# homeboard16.net
KiCad netlist of a schematic drawn in EAGLE
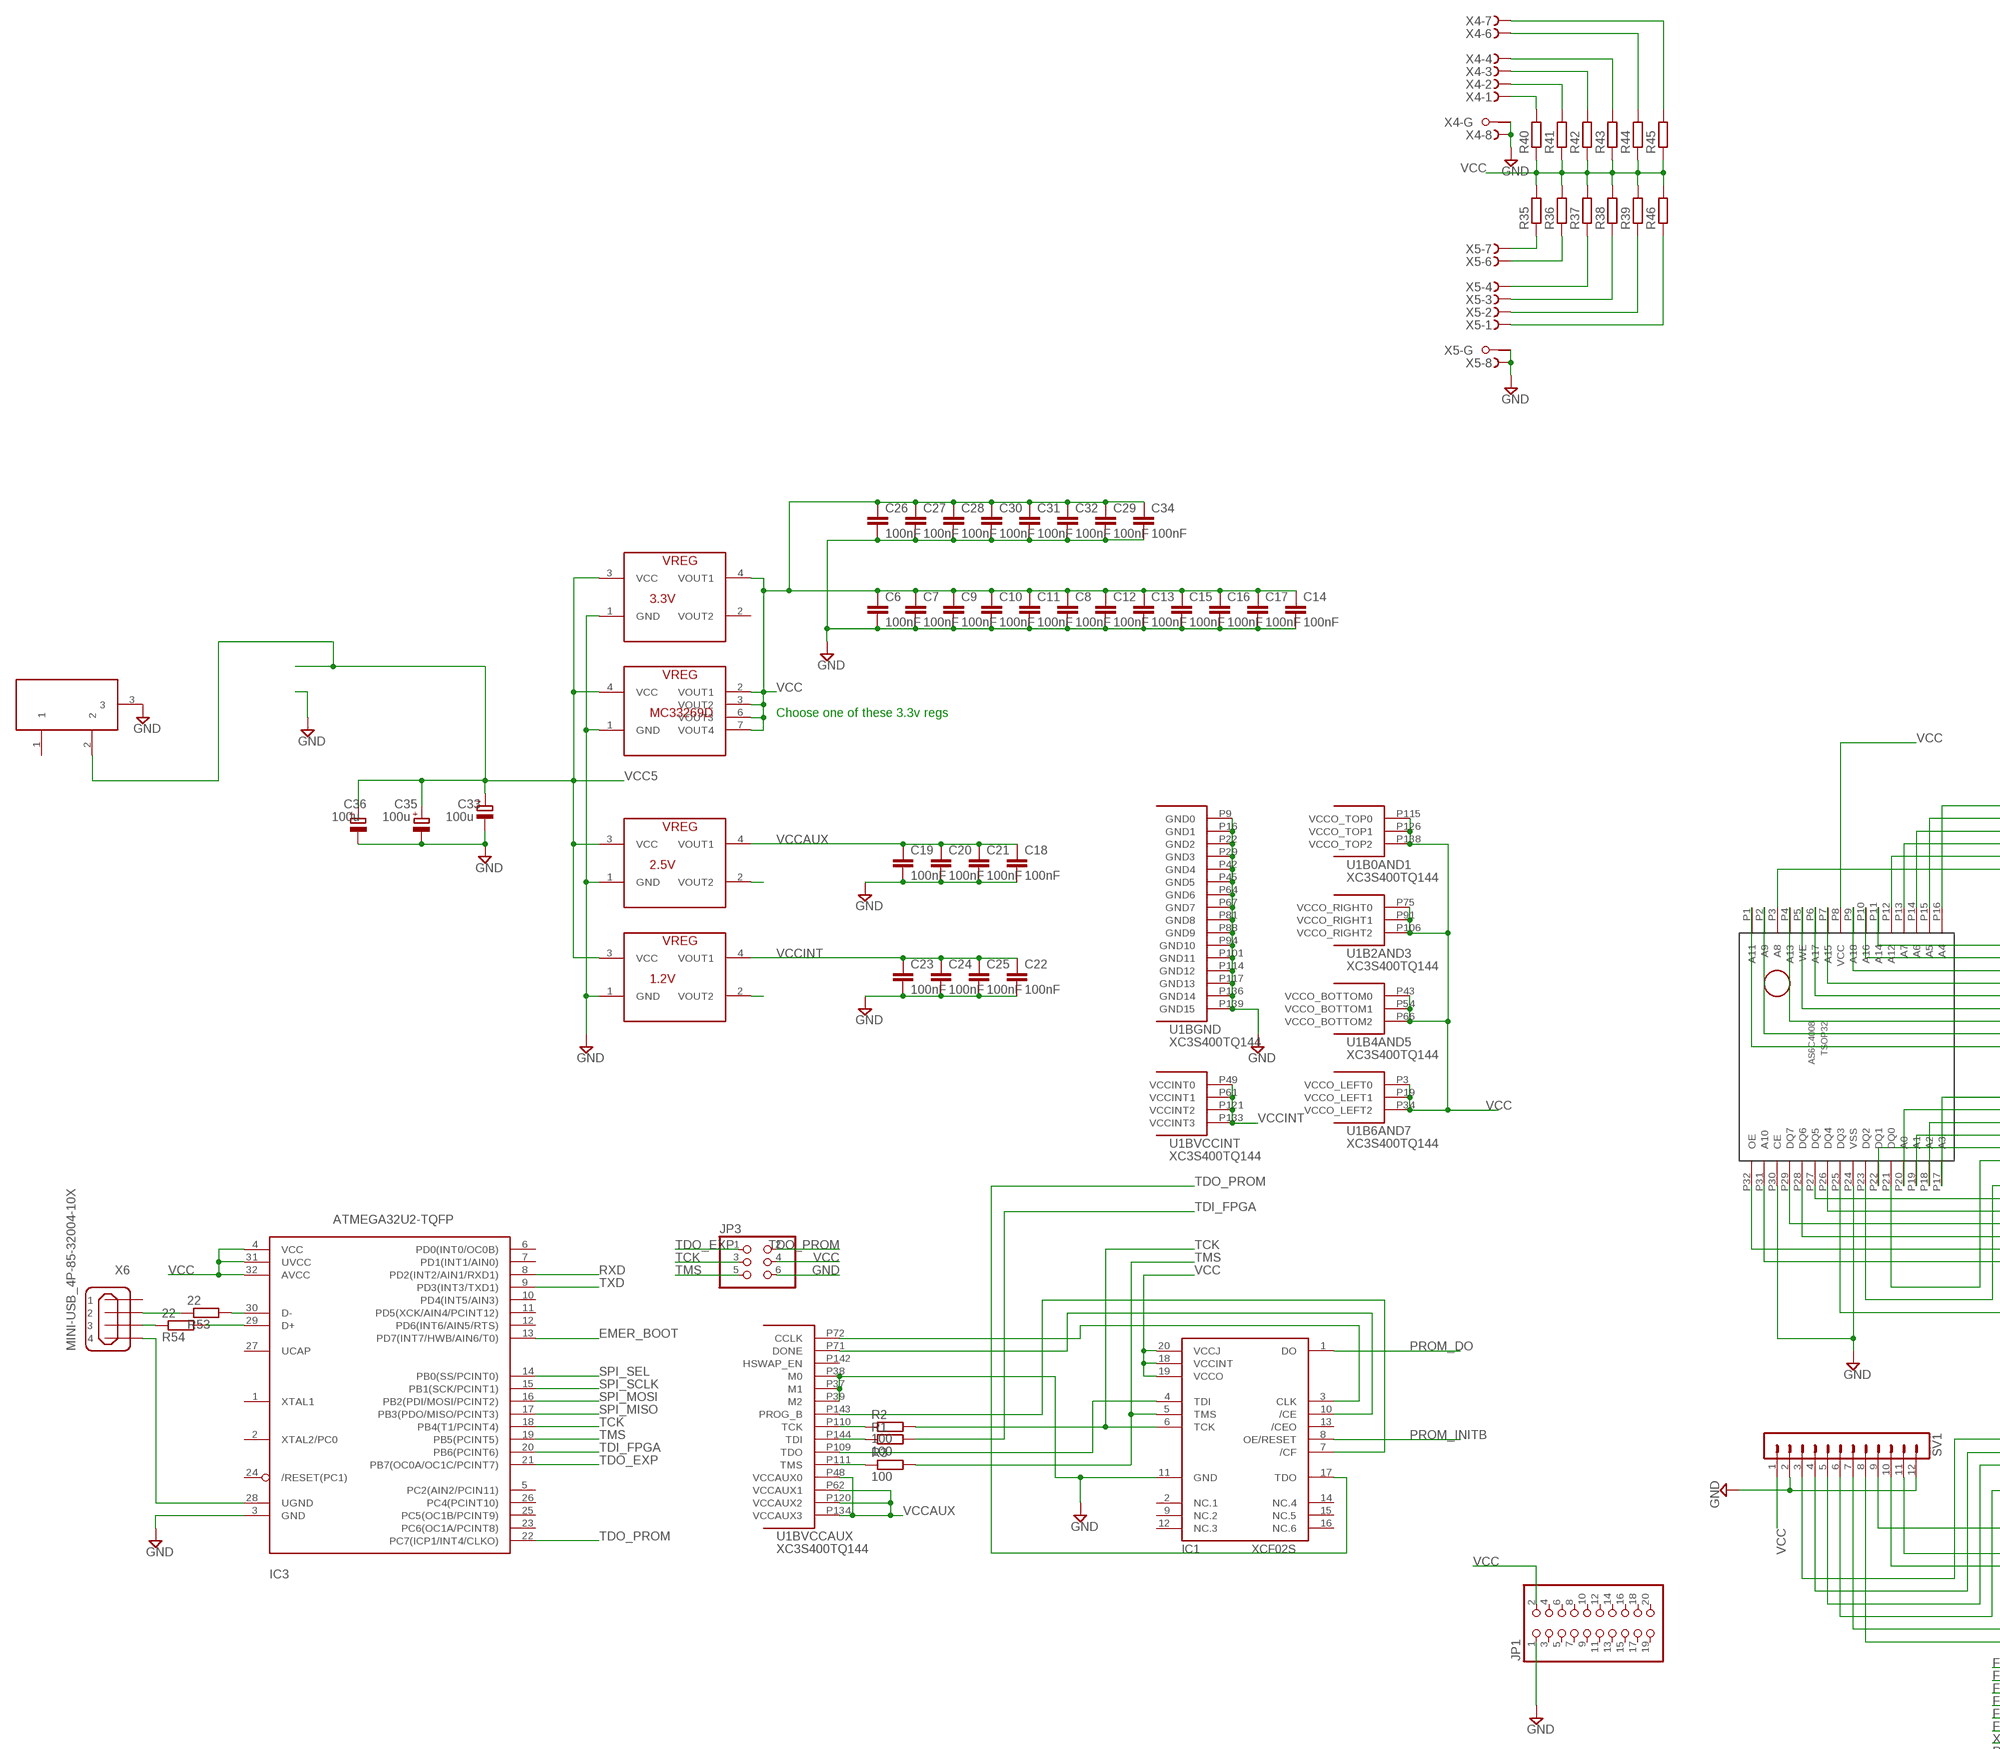
[diagram p0: schematic, sheet 1, part 1 of 3]
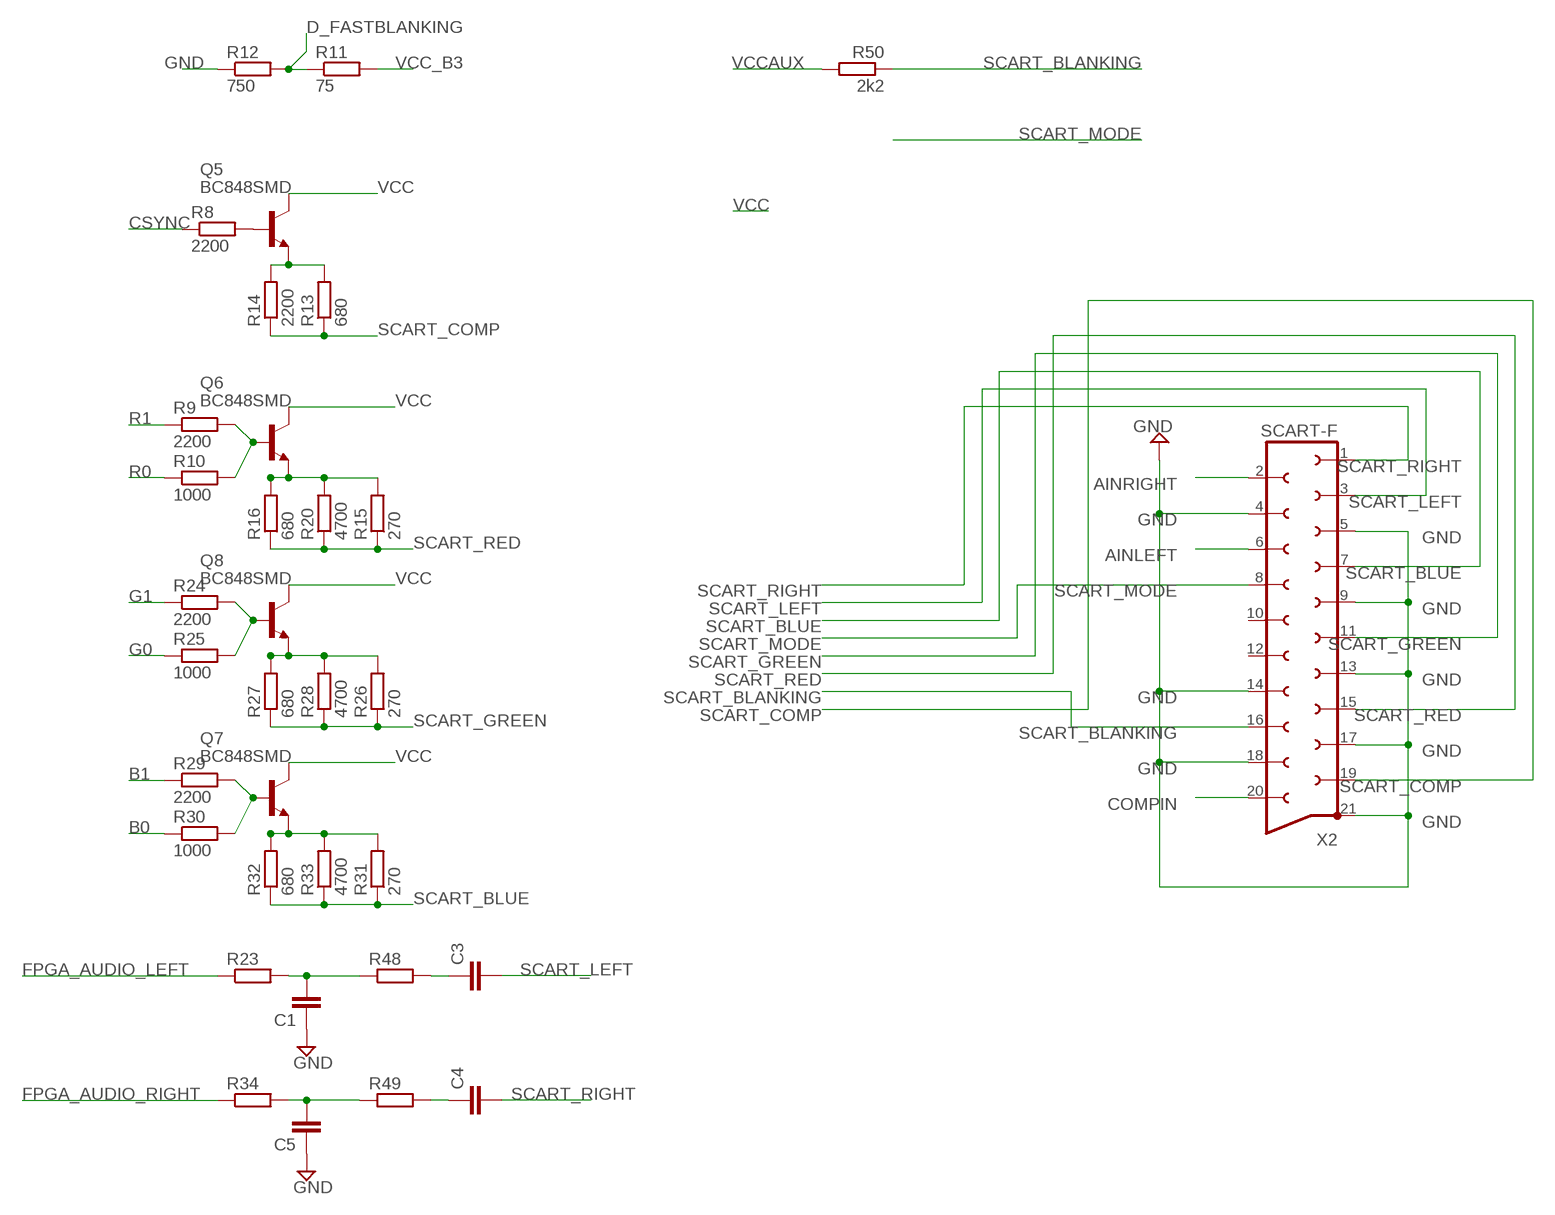
[diagram p1: schematic, sheet 1, part 2 of 3]
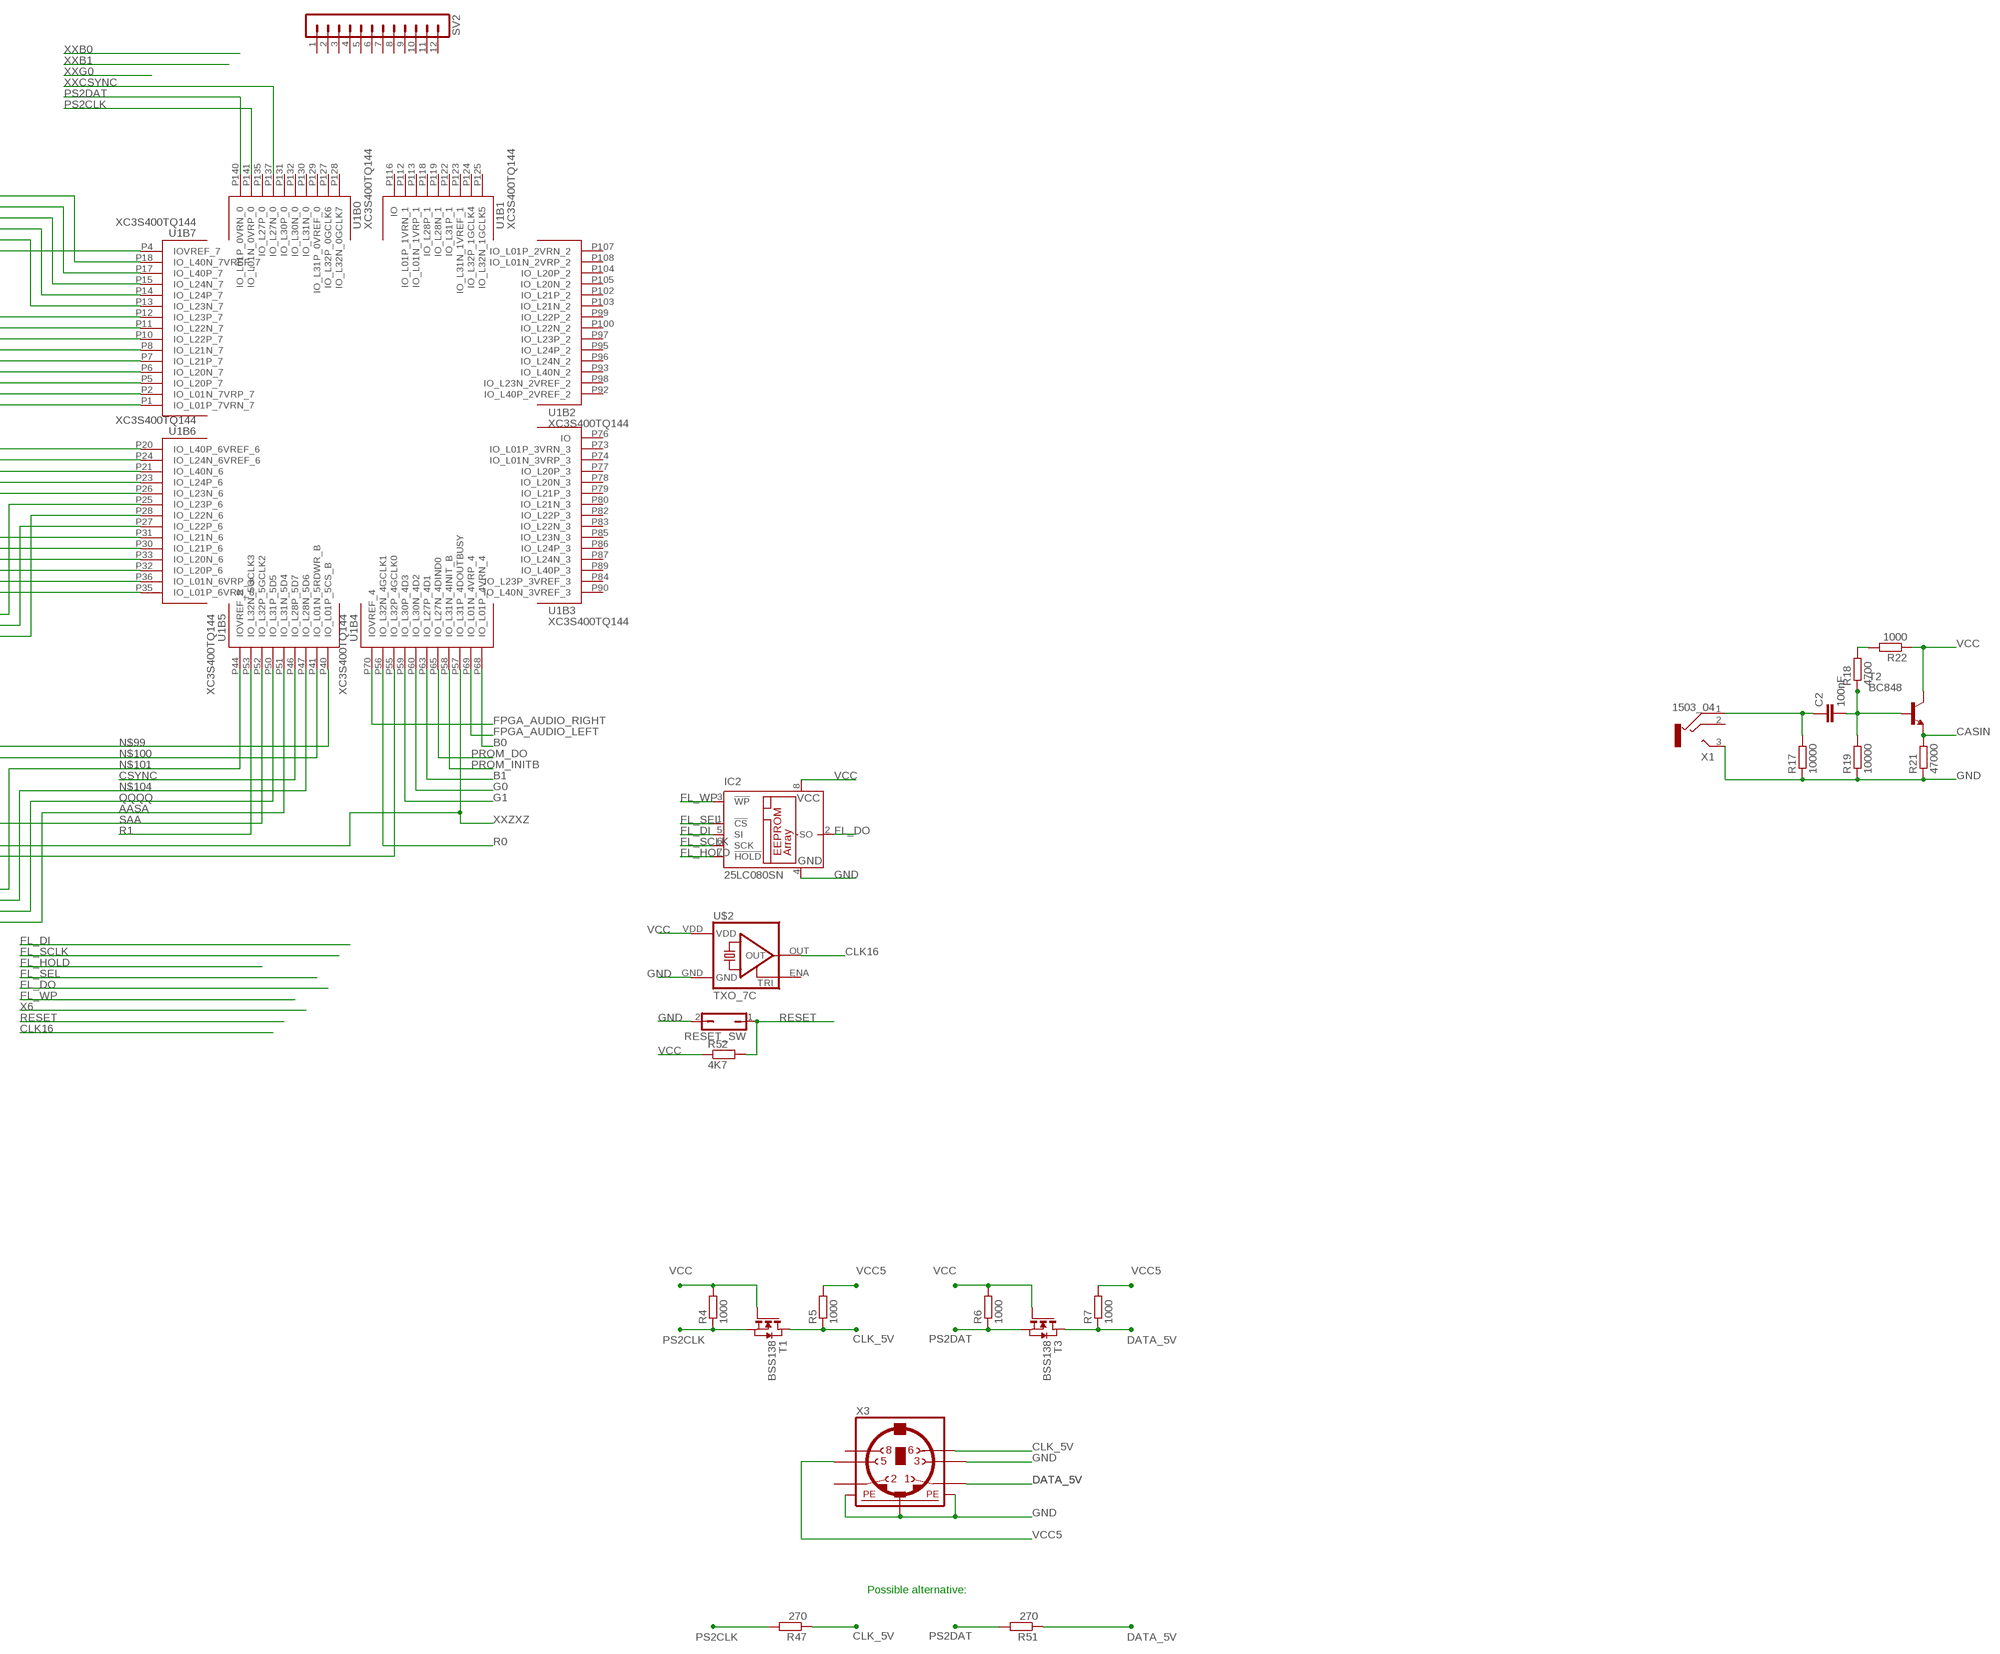
[diagram p2: schematic, sheet 1, part 3 of 3]

(export (version "E")
  (design (tool "Eeschema 10.0.6"))
  (components
    (comp (ref "C1")
      (value "C-EUC0603")
      (footprint "eagle-import:C0603")
      (libsource (lib "eagle-import") (part "resistor_C-EUC0603"))
    )
    (comp (ref "C2")
      (value "100nF")
      (footprint "eagle-import:C0603")
      (libsource (lib "eagle-import") (part "resistor_C-EUC0603"))
    )
    (comp (ref "C3")
      (value "C-EUC0603")
      (footprint "eagle-import:C0603")
      (libsource (lib "eagle-import") (part "resistor_C-EUC0603"))
    )
    (comp (ref "C4")
      (value "C-EUC0603")
      (footprint "eagle-import:C0603")
      (libsource (lib "eagle-import") (part "resistor_C-EUC0603"))
    )
    (comp (ref "C5")
      (value "C-EUC0603")
      (footprint "eagle-import:C0603")
      (libsource (lib "eagle-import") (part "resistor_C-EUC0603"))
    )
    (comp (ref "C6")
      (value "100nF")
      (footprint "eagle-import:C0603")
      (libsource (lib "eagle-import") (part "C-EUC0603"))
    )
    (comp (ref "C7")
      (value "100nF")
      (footprint "eagle-import:C0603")
      (libsource (lib "eagle-import") (part "C-EUC0603"))
    )
    (comp (ref "C8")
      (value "100nF")
      (footprint "eagle-import:C0603")
      (libsource (lib "eagle-import") (part "C-EUC0603"))
    )
    (comp (ref "C9")
      (value "100nF")
      (footprint "eagle-import:C0603")
      (libsource (lib "eagle-import") (part "C-EUC0603"))
    )
    (comp (ref "C10")
      (value "100nF")
      (footprint "eagle-import:C0603")
      (libsource (lib "eagle-import") (part "C-EUC0603"))
    )
    (comp (ref "C11")
      (value "100nF")
      (footprint "eagle-import:C0603")
      (libsource (lib "eagle-import") (part "C-EUC0603"))
    )
    (comp (ref "C12")
      (value "100nF")
      (footprint "eagle-import:C0603")
      (libsource (lib "eagle-import") (part "C-EUC0603"))
    )
    (comp (ref "C13")
      (value "100nF")
      (footprint "eagle-import:C0603")
      (libsource (lib "eagle-import") (part "C-EUC0603"))
    )
    (comp (ref "C14")
      (value "100nF")
      (footprint "eagle-import:C0603")
      (libsource (lib "eagle-import") (part "C-EUC0603"))
    )
    (comp (ref "C15")
      (value "100nF")
      (footprint "eagle-import:C0603")
      (libsource (lib "eagle-import") (part "C-EUC0603"))
    )
    (comp (ref "C16")
      (value "100nF")
      (footprint "eagle-import:C0603")
      (libsource (lib "eagle-import") (part "C-EUC0603"))
    )
    (comp (ref "C17")
      (value "100nF")
      (footprint "eagle-import:C0603")
      (libsource (lib "eagle-import") (part "C-EUC0603"))
    )
    (comp (ref "C18")
      (value "100nF")
      (footprint "eagle-import:C0603")
      (libsource (lib "eagle-import") (part "C-EUC0603"))
    )
    (comp (ref "C19")
      (value "100nF")
      (footprint "eagle-import:C0603")
      (libsource (lib "eagle-import") (part "C-EUC0603"))
    )
    (comp (ref "C20")
      (value "100nF")
      (footprint "eagle-import:C0603")
      (libsource (lib "eagle-import") (part "C-EUC0603"))
    )
    (comp (ref "C21")
      (value "100nF")
      (footprint "eagle-import:C0603")
      (libsource (lib "eagle-import") (part "C-EUC0603"))
    )
    (comp (ref "C22")
      (value "100nF")
      (footprint "eagle-import:C0603")
      (libsource (lib "eagle-import") (part "C-EUC0603"))
    )
    (comp (ref "C23")
      (value "100nF")
      (footprint "eagle-import:C0603")
      (libsource (lib "eagle-import") (part "C-EUC0603"))
    )
    (comp (ref "C24")
      (value "100nF")
      (footprint "eagle-import:C0603")
      (libsource (lib "eagle-import") (part "C-EUC0603"))
    )
    (comp (ref "C25")
      (value "100nF")
      (footprint "eagle-import:C0603")
      (libsource (lib "eagle-import") (part "C-EUC0603"))
    )
    (comp (ref "C26")
      (value "100nF")
      (footprint "eagle-import:C0603")
      (libsource (lib "eagle-import") (part "C-EUC0603"))
    )
    (comp (ref "C27")
      (value "100nF")
      (footprint "eagle-import:C0603")
      (libsource (lib "eagle-import") (part "C-EUC0603"))
    )
    (comp (ref "C28")
      (value "100nF")
      (footprint "eagle-import:C0603")
      (libsource (lib "eagle-import") (part "C-EUC0603"))
    )
    (comp (ref "C29")
      (value "100nF")
      (footprint "eagle-import:C0603")
      (libsource (lib "eagle-import") (part "C-EUC0603"))
    )
    (comp (ref "C30")
      (value "100nF")
      (footprint "eagle-import:C0603")
      (libsource (lib "eagle-import") (part "C-EUC0603"))
    )
    (comp (ref "C31")
      (value "100nF")
      (footprint "eagle-import:C0603")
      (libsource (lib "eagle-import") (part "C-EUC0603"))
    )
    (comp (ref "C32")
      (value "100nF")
      (footprint "eagle-import:C0603")
      (libsource (lib "eagle-import") (part "C-EUC0603"))
    )
    (comp (ref "C33")
      (value "100u")
      (footprint "eagle-import:PANASONIC_D")
      (libsource (lib "eagle-import") (part "CPOL-EUD"))
    )
    (comp (ref "C34")
      (value "100nF")
      (footprint "eagle-import:C0603")
      (libsource (lib "eagle-import") (part "C-EUC0603"))
    )
    (comp (ref "C35")
      (value "100u")
      (footprint "eagle-import:PANASONIC_D")
      (libsource (lib "eagle-import") (part "CPOL-EUD"))
    )
    (comp (ref "C36")
      (value "100u")
      (footprint "eagle-import:PANASONIC_D")
      (libsource (lib "eagle-import") (part "CPOL-EUD"))
    )
    (comp (ref "IC1")
      (value "XCF02S")
      (footprint "eagle-import:VO20")
      (libsource (lib "eagle-import") (part "XCF02S"))
    )
    (comp (ref "IC2")
      (value "25LC080SN")
      (footprint "eagle-import:SO-08")
      (fields (field (name "MF") "MICROCHIP") (field (name "MPN") "25LC080/SN"))
      (libsource (lib "eagle-import") (part "25SNLC080"))
    )
    (comp (ref "IC3")
      (value "ATMEGA32U2-TQFP")
      (footprint "eagle-import:TQFP32-08")
      (libsource (lib "eagle-import") (part "ATMEGA32U2-TQFP"))
    )
    (comp (ref "JP1")
      (value "PINHD-2X10")
      (footprint "eagle-import:2X10")
      (libsource (lib "eagle-import") (part "PINHD-2X10"))
    )
    (comp (ref "JP3")
      (value "PINHD-2X3")
      (footprint "eagle-import:2X03")
      (libsource (lib "eagle-import") (part "PINHD-2X3"))
    )
    (comp (ref "Q5")
      (value "BC848SMD")
      (footprint "eagle-import:SOT23")
      (libsource (lib "eagle-import") (part "BC848SMD"))
    )
    (comp (ref "Q6")
      (value "BC848SMD")
      (footprint "eagle-import:SOT23")
      (libsource (lib "eagle-import") (part "BC848SMD"))
    )
    (comp (ref "Q7")
      (value "BC848SMD")
      (footprint "eagle-import:SOT23")
      (libsource (lib "eagle-import") (part "BC848SMD"))
    )
    (comp (ref "Q8")
      (value "BC848SMD")
      (footprint "eagle-import:SOT23")
      (libsource (lib "eagle-import") (part "BC848SMD"))
    )
    (comp (ref "R1")
      (value "100")
      (footprint "eagle-import:R0805")
      (libsource (lib "eagle-import") (part "R-EU_R0805"))
    )
    (comp (ref "R2")
      (value "100")
      (footprint "eagle-import:R0805")
      (libsource (lib "eagle-import") (part "R-EU_R0805"))
    )
    (comp (ref "R3")
      (value "100")
      (footprint "eagle-import:R0805")
      (libsource (lib "eagle-import") (part "R-EU_R0805"))
    )
    (comp (ref "R4")
      (value "1000")
      (footprint "eagle-import:R0805")
      (libsource (lib "eagle-import") (part "R-EU_R0805"))
    )
    (comp (ref "R5")
      (value "1000")
      (footprint "eagle-import:R0805")
      (libsource (lib "eagle-import") (part "R-EU_R0805"))
    )
    (comp (ref "R6")
      (value "1000")
      (footprint "eagle-import:R0805")
      (libsource (lib "eagle-import") (part "R-EU_R0805"))
    )
    (comp (ref "R7")
      (value "1000")
      (footprint "eagle-import:R0805")
      (libsource (lib "eagle-import") (part "R-EU_R0805"))
    )
    (comp (ref "R8")
      (value "2200")
      (footprint "eagle-import:R0805")
      (libsource (lib "eagle-import") (part "R-EU_R0805"))
    )
    (comp (ref "R9")
      (value "2200")
      (footprint "eagle-import:R0805")
      (libsource (lib "eagle-import") (part "R-EU_R0805"))
    )
    (comp (ref "R10")
      (value "1000")
      (footprint "eagle-import:R0805")
      (libsource (lib "eagle-import") (part "R-EU_R0805"))
    )
    (comp (ref "R11")
      (value "75")
      (footprint "eagle-import:R0805")
      (libsource (lib "eagle-import") (part "R-EU_R0805"))
    )
    (comp (ref "R12")
      (value "750")
      (footprint "eagle-import:R0805")
      (libsource (lib "eagle-import") (part "R-EU_R0805"))
    )
    (comp (ref "R13")
      (value "680")
      (footprint "eagle-import:R0805")
      (libsource (lib "eagle-import") (part "R-EU_R0805"))
    )
    (comp (ref "R14")
      (value "2200")
      (footprint "eagle-import:R0805")
      (libsource (lib "eagle-import") (part "R-EU_R0805"))
    )
    (comp (ref "R15")
      (value "270")
      (footprint "eagle-import:R0805")
      (libsource (lib "eagle-import") (part "R-EU_R0805"))
    )
    (comp (ref "R16")
      (value "680")
      (footprint "eagle-import:R0805")
      (libsource (lib "eagle-import") (part "R-EU_R0805"))
    )
    (comp (ref "R17")
      (value "10000")
      (footprint "eagle-import:R0805")
      (libsource (lib "eagle-import") (part "R-EU_R0805"))
    )
    (comp (ref "R18")
      (value "4700")
      (footprint "eagle-import:R0805")
      (libsource (lib "eagle-import") (part "R-EU_R0805"))
    )
    (comp (ref "R19")
      (value "10000")
      (footprint "eagle-import:R0805")
      (libsource (lib "eagle-import") (part "R-EU_R0805"))
    )
    (comp (ref "R20")
      (value "4700")
      (footprint "eagle-import:R0805")
      (libsource (lib "eagle-import") (part "R-EU_R0805"))
    )
    (comp (ref "R21")
      (value "47000")
      (footprint "eagle-import:R0805")
      (libsource (lib "eagle-import") (part "R-EU_R0805"))
    )
    (comp (ref "R22")
      (value "1000")
      (footprint "eagle-import:R0805")
      (libsource (lib "eagle-import") (part "R-EU_R0805"))
    )
    (comp (ref "R23")
      (value "R-EU_M0805")
      (footprint "eagle-import:M0805")
      (libsource (lib "eagle-import") (part "resistor_R-EU_M0805"))
    )
    (comp (ref "R24")
      (value "2200")
      (footprint "eagle-import:R0805")
      (libsource (lib "eagle-import") (part "R-EU_R0805"))
    )
    (comp (ref "R25")
      (value "1000")
      (footprint "eagle-import:R0805")
      (libsource (lib "eagle-import") (part "R-EU_R0805"))
    )
    (comp (ref "R26")
      (value "270")
      (footprint "eagle-import:R0805")
      (libsource (lib "eagle-import") (part "R-EU_R0805"))
    )
    (comp (ref "R27")
      (value "680")
      (footprint "eagle-import:R0805")
      (libsource (lib "eagle-import") (part "R-EU_R0805"))
    )
    (comp (ref "R28")
      (value "4700")
      (footprint "eagle-import:R0805")
      (libsource (lib "eagle-import") (part "R-EU_R0805"))
    )
    (comp (ref "R29")
      (value "2200")
      (footprint "eagle-import:R0805")
      (libsource (lib "eagle-import") (part "R-EU_R0805"))
    )
    (comp (ref "R30")
      (value "1000")
      (footprint "eagle-import:R0805")
      (libsource (lib "eagle-import") (part "R-EU_R0805"))
    )
    (comp (ref "R31")
      (value "270")
      (footprint "eagle-import:R0805")
      (libsource (lib "eagle-import") (part "R-EU_R0805"))
    )
    (comp (ref "R32")
      (value "680")
      (footprint "eagle-import:R0805")
      (libsource (lib "eagle-import") (part "R-EU_R0805"))
    )
    (comp (ref "R33")
      (value "4700")
      (footprint "eagle-import:R0805")
      (libsource (lib "eagle-import") (part "R-EU_R0805"))
    )
    (comp (ref "R34")
      (value "R-EU_M0805")
      (footprint "eagle-import:M0805")
      (libsource (lib "eagle-import") (part "resistor_R-EU_M0805"))
    )
    (comp (ref "R35")
      (value "R-EU_M0805")
      (footprint "eagle-import:M0805")
      (libsource (lib "eagle-import") (part "resistor_R-EU_M0805"))
    )
    (comp (ref "R36")
      (value "R-EU_M0805")
      (footprint "eagle-import:M0805")
      (libsource (lib "eagle-import") (part "resistor_R-EU_M0805"))
    )
    (comp (ref "R37")
      (value "R-EU_M0805")
      (footprint "eagle-import:M0805")
      (libsource (lib "eagle-import") (part "resistor_R-EU_M0805"))
    )
    (comp (ref "R38")
      (value "R-EU_M0805")
      (footprint "eagle-import:M0805")
      (libsource (lib "eagle-import") (part "resistor_R-EU_M0805"))
    )
    (comp (ref "R39")
      (value "R-EU_M0805")
      (footprint "eagle-import:M0805")
      (libsource (lib "eagle-import") (part "resistor_R-EU_M0805"))
    )
    (comp (ref "R40")
      (value "R-EU_M0805")
      (footprint "eagle-import:M0805")
      (libsource (lib "eagle-import") (part "resistor_R-EU_M0805"))
    )
    (comp (ref "R41")
      (value "R-EU_M0805")
      (footprint "eagle-import:M0805")
      (libsource (lib "eagle-import") (part "resistor_R-EU_M0805"))
    )
    (comp (ref "R42")
      (value "R-EU_M0805")
      (footprint "eagle-import:M0805")
      (libsource (lib "eagle-import") (part "resistor_R-EU_M0805"))
    )
    (comp (ref "R43")
      (value "R-EU_M0805")
      (footprint "eagle-import:M0805")
      (libsource (lib "eagle-import") (part "resistor_R-EU_M0805"))
    )
    (comp (ref "R44")
      (value "R-EU_M0805")
      (footprint "eagle-import:M0805")
      (libsource (lib "eagle-import") (part "resistor_R-EU_M0805"))
    )
    (comp (ref "R45")
      (value "R-EU_M0805")
      (footprint "eagle-import:M0805")
      (libsource (lib "eagle-import") (part "resistor_R-EU_M0805"))
    )
    (comp (ref "R46")
      (value "R-EU_M0805")
      (footprint "eagle-import:M0805")
      (libsource (lib "eagle-import") (part "resistor_R-EU_M0805"))
    )
    (comp (ref "R47")
      (value "270")
      (footprint "eagle-import:R0805")
      (libsource (lib "eagle-import") (part "R-EU_R0805"))
    )
    (comp (ref "R48")
      (value "R-EU_M0805")
      (footprint "eagle-import:M0805")
      (libsource (lib "eagle-import") (part "resistor_R-EU_M0805"))
    )
    (comp (ref "R49")
      (value "R-EU_M0805")
      (footprint "eagle-import:M0805")
      (libsource (lib "eagle-import") (part "resistor_R-EU_M0805"))
    )
    (comp (ref "R50")
      (value "2k2")
      (footprint "eagle-import:M0805")
      (libsource (lib "eagle-import") (part "resistor_R-EU_M0805"))
    )
    (comp (ref "R51")
      (value "270")
      (footprint "eagle-import:R0805")
      (libsource (lib "eagle-import") (part "R-EU_R0805"))
    )
    (comp (ref "R52")
      (value "4K7")
      (footprint "eagle-import:M0805")
      (libsource (lib "eagle-import") (part "resistor_R-EU_M0805"))
    )
    (comp (ref "R53")
      (value "22")
      (footprint "eagle-import:R0805")
      (libsource (lib "eagle-import") (part "R-EU_R0805"))
    )
    (comp (ref "R54")
      (value "22")
      (footprint "eagle-import:R0805")
      (libsource (lib "eagle-import") (part "R-EU_R0805"))
    )
    (comp (ref "REG1.2")
      (value "1.2V")
      (footprint "eagle-import:SOT223")
      (libsource (lib "eagle-import") (part "NX1117"))
    )
    (comp (ref "REG2.5")
      (value "2.5V")
      (footprint "eagle-import:SOT223")
      (libsource (lib "eagle-import") (part "NX1117"))
    )
    (comp (ref "RESET_SW")
      (value "JP1Q")
      (footprint "eagle-import:JP1")
      (libsource (lib "eagle-import") (part "JP1Q"))
    )
    (comp (ref "SV1")
      (value "MA12-1")
      (footprint "eagle-import:MA12-1")
      (libsource (lib "eagle-import") (part "MA12-1"))
    )
    (comp (ref "SV2")
      (value "MA12-1")
      (footprint "eagle-import:MA12-1")
      (fields (field (name "OC_FARNELL") "unknown") (field (name "OC_NEWARK") "unknown"))
      (libsource (lib "eagle-import") (part "MA12-1"))
    )
    (comp (ref "T1")
      (value "BSS138")
      (footprint "eagle-import:SOT-23")
      (libsource (lib "eagle-import") (part "NMOSSOT23"))
    )
    (comp (ref "T2")
      (value "BC848")
      (footprint "eagle-import:SOT23")
      (libsource (lib "eagle-import") (part "BC848"))
    )
    (comp (ref "T3")
      (value "BSS138")
      (footprint "eagle-import:SOT-23")
      (libsource (lib "eagle-import") (part "NMOSSOT23"))
    )
    (comp (ref "U$2")
      (value "TXO_7C")
      (footprint "eagle-import:OSC_7C")
      (libsource (lib "eagle-import") (part "TXO_7C"))
    )
    (comp (ref "U$4")
      (value "3.3V")
      (footprint "eagle-import:SOT223")
      (libsource (lib "eagle-import") (part "NX1117"))
    )
    (comp (ref "U$5")
      (value "MC33269D")
      (footprint "eagle-import:SO8")
      (libsource (lib "eagle-import") (part "MC33269D"))
    )
    (comp (ref "U$6")
      (value "AS6C4008")
      (footprint "eagle-import:TSOP32")
      (libsource (lib "eagle-import") (part "AS6C4008"))
    )
    (comp (ref "U1")
      (value "XC3S400TQ144")
      (footprint "eagle-import:TQ144")
      (libsource (lib "eagle-import") (part "XC3S400TQ144"))
    )
    (comp (ref "X1")
      (value "1503_04")
      (footprint "eagle-import:1503_04")
      (libsource (lib "eagle-import") (part "1503_04"))
    )
    (comp (ref "X2")
      (value "SCART-F")
      (footprint "eagle-import:SCART-F")
      (libsource (lib "eagle-import") (part "SCART-F"))
    )
    (comp (ref "X3")
      (value "MINI_DIN_6")
      (footprint "eagle-import:M_DIN6")
      (libsource (lib "eagle-import") (part "MINI_DIN_6"))
    )
    (comp (ref "X4")
      (value "F09HPS")
      (footprint "eagle-import:F09HP")
      (libsource (lib "eagle-import") (part "F09HPS"))
    )
    (comp (ref "X5")
      (value "F09HPS")
      (footprint "eagle-import:F09HP")
      (libsource (lib "eagle-import") (part "F09HPS"))
    )
    (comp (ref "X6")
      (value "MINI-USB_4P-85-32004-10X")
      (footprint "eagle-import:85-32004-10X")
      (libsource (lib "eagle-import") (part "MINI-USB_4P-85-32004-10X"))
    )
    (comp (ref "X7")
      (value "DC21MMX")
      (footprint "eagle-import:DC-21MM")
      (libsource (lib "eagle-import") (part "DC21MMX"))
    )
  )
  (nets
    (net (code "1") (name "/1") (class "Default")
      (node (ref "X7") (pin "1") (pinfunction "1_1") (pintype "power_in"))
    )
    (net (code "2") (name "/AASA") (class "Default")
      (node (ref "SV1") (pin "8") (pinfunction "8_8") (pintype "passive"))
      (node (ref "U1") (pin "P51") (pinfunction "IO_L31N_5D4_P51") (pintype "bidirectional"))
    )
    (net (code "3") (name "/AINLEFT") (class "Default")
      (node (ref "X2") (pin "6") (pinfunction "6_6") (pintype "passive"))
    )
    (net (code "4") (name "/AINRIGHT") (class "Default")
      (node (ref "X2") (pin "2") (pinfunction "2_2") (pintype "passive"))
    )
    (net (code "5") (name "/B0") (class "Default")
      (node (ref "R30") (pin "1") (pinfunction "1_1") (pintype "passive"))
      (node (ref "U1") (pin "P68") (pinfunction "IO_L01P_4VRN_4_P68") (pintype "bidirectional"))
    )
    (net (code "6") (name "/B1") (class "Default")
      (node (ref "R29") (pin "1") (pinfunction "1_1") (pintype "passive"))
      (node (ref "U1") (pin "P63") (pinfunction "IO_L27P_4D1_P63") (pintype "bidirectional"))
    )
    (net (code "7") (name "/CASIN") (class "Default")
      (node (ref "R21") (pin "2") (pinfunction "2_2") (pintype "passive"))
      (node (ref "T2") (pin "2") (pinfunction "E_2") (pintype "passive"))
    )
    (net (code "8") (name "/CLK16") (class "Default")
      (node (ref "U$2") (pin "OUT") (pinfunction "OUT_OUT") (pintype "output"))
    )
    (net (code "9") (name "/CLK_5V") (class "Default")
      (node (ref "R47") (pin "1") (pinfunction "1_1") (pintype "passive"))
      (node (ref "R5") (pin "1") (pinfunction "1_1") (pintype "passive"))
      (node (ref "T1") (pin "1") (pinfunction "D_1") (pintype "passive"))
      (node (ref "X3") (pin "6") (pinfunction "6_6") (pintype "passive"))
    )
    (net (code "10") (name "/COMPIN") (class "Default")
      (node (ref "X2") (pin "20") (pinfunction "20_20") (pintype "passive"))
    )
    (net (code "11") (name "/CSYNC") (class "Default")
      (node (ref "R8") (pin "1") (pinfunction "1_1") (pintype "passive"))
      (node (ref "U1") (pin "P46") (pinfunction "IO_L28P_5D7_P46") (pintype "bidirectional"))
    )
    (net (code "12") (name "/DATA_5V") (class "Default")
      (node (ref "R51") (pin "1") (pinfunction "1_1") (pintype "passive"))
      (node (ref "R7") (pin "1") (pinfunction "1_1") (pintype "passive"))
      (node (ref "T3") (pin "1") (pinfunction "D_1") (pintype "passive"))
      (node (ref "X3") (pin "1") (pinfunction "1_1") (pintype "passive"))
    )
    (net (code "13") (name "/D_FASTBLANKING") (class "Default")
      (node (ref "R11") (pin "1") (pinfunction "1_1") (pintype "passive"))
      (node (ref "R12") (pin "2") (pinfunction "2_2") (pintype "passive"))
    )
    (net (code "14") (name "/EMER_BOOT") (class "Default")
      (node (ref "IC3") (pin "13") (pinfunction "PD7(INT7/HWB/AIN6/T0)_13") (pintype "bidirectional"))
    )
    (net (code "15") (name "/FL_DI") (class "Default")
      (node (ref "IC2") (pin "5") (pinfunction "SI_5") (pintype "input"))
    )
    (net (code "16") (name "/FL_DO") (class "Default")
      (node (ref "IC2") (pin "2") (pinfunction "SO_2") (pintype "bidirectional"))
    )
    (net (code "17") (name "/FL_HOLD") (class "Default")
      (node (ref "IC2") (pin "7") (pinfunction "~{HOLD}_7") (pintype "input"))
    )
    (net (code "18") (name "/FL_SCLK") (class "Default")
      (node (ref "IC2") (pin "6") (pinfunction "SCK_6") (pintype "input"))
    )
    (net (code "19") (name "/FL_SEL") (class "Default")
      (node (ref "IC2") (pin "1") (pinfunction "~{CS}_1") (pintype "input"))
    )
    (net (code "20") (name "/FL_WP") (class "Default")
      (node (ref "IC2") (pin "3") (pinfunction "~{WP}_3") (pintype "input"))
    )
    (net (code "21") (name "/FPGA_AUDIO_LEFT") (class "Default")
      (node (ref "R23") (pin "1") (pinfunction "1_1") (pintype "passive"))
      (node (ref "U1") (pin "P69") (pinfunction "IO_L01N_4VRP_4_P69") (pintype "bidirectional"))
    )
    (net (code "22") (name "/FPGA_AUDIO_RIGHT") (class "Default")
      (node (ref "R34") (pin "1") (pinfunction "1_1") (pintype "passive"))
      (node (ref "U1") (pin "P70") (pinfunction "IOVREF_4_P70") (pintype "bidirectional"))
    )
    (net (code "23") (name "/G0") (class "Default")
      (node (ref "R25") (pin "1") (pinfunction "1_1") (pintype "passive"))
      (node (ref "U1") (pin "P60") (pinfunction "IO_L30N_4D2_P60") (pintype "bidirectional"))
    )
    (net (code "24") (name "/G1") (class "Default")
      (node (ref "R24") (pin "1") (pinfunction "1_1") (pintype "passive"))
      (node (ref "U1") (pin "P59") (pinfunction "IO_L30P_4D3_P59") (pintype "bidirectional"))
    )
    (net (code "25") (name "/N$99") (class "Default")
      (node (ref "SV1") (pin "3") (pinfunction "3_3") (pintype "passive"))
      (node (ref "U1") (pin "P40") (pinfunction "IO_L01P_5CS_B_P40") (pintype "bidirectional"))
    )
    (net (code "26") (name "/N$100") (class "Default")
      (node (ref "SV1") (pin "4") (pinfunction "4_4") (pintype "passive"))
      (node (ref "U1") (pin "P41") (pinfunction "IO_L01N_5RDWR_B_P41") (pintype "bidirectional"))
    )
    (net (code "27") (name "/N$101") (class "Default")
      (node (ref "SV1") (pin "5") (pinfunction "5_5") (pintype "passive"))
      (node (ref "U1") (pin "P44") (pinfunction "IOVREF_5_P44") (pintype "bidirectional"))
    )
    (net (code "28") (name "/N$104") (class "Default")
      (node (ref "SV1") (pin "6") (pinfunction "6_6") (pintype "passive"))
      (node (ref "U1") (pin "P47") (pinfunction "IO_L28N_5D6_P47") (pintype "bidirectional"))
    )
    (net (code "29") (name "/PROM_DO") (class "Default")
      (node (ref "IC1") (pin "1") (pinfunction "DO_1") (pintype "bidirectional"))
      (node (ref "U1") (pin "P65") (pinfunction "IO_L27N_4DIND0_P65") (pintype "bidirectional"))
    )
    (net (code "30") (name "/PROM_INITB") (class "Default")
      (node (ref "IC1") (pin "8") (pinfunction "OE/RESET_8") (pintype "bidirectional"))
      (node (ref "U1") (pin "P58") (pinfunction "IO_L31N_4INIT_B_P58") (pintype "bidirectional"))
    )
    (net (code "31") (name "/PS2CLK") (class "Default")
      (node (ref "R4") (pin "1") (pinfunction "1_1") (pintype "passive"))
      (node (ref "R47") (pin "2") (pinfunction "2_2") (pintype "passive"))
      (node (ref "T1") (pin "2") (pinfunction "S_2") (pintype "passive"))
      (node (ref "U1") (pin "P141") (pinfunction "IO_L01N_0VRP_0_P141") (pintype "bidirectional"))
    )
    (net (code "32") (name "/PS2DAT") (class "Default")
      (node (ref "R51") (pin "2") (pinfunction "2_2") (pintype "passive"))
      (node (ref "R6") (pin "1") (pinfunction "1_1") (pintype "passive"))
      (node (ref "T3") (pin "2") (pinfunction "S_2") (pintype "passive"))
      (node (ref "U1") (pin "P140") (pinfunction "IO_L01P_0VRN_0_P140") (pintype "bidirectional"))
    )
    (net (code "33") (name "/QQQQ") (class "Default")
      (node (ref "SV1") (pin "7") (pinfunction "7_7") (pintype "passive"))
      (node (ref "U1") (pin "P50") (pinfunction "IO_L31P_5D5_P50") (pintype "bidirectional"))
    )
    (net (code "34") (name "/R0") (class "Default")
      (node (ref "R10") (pin "1") (pinfunction "1_1") (pintype "passive"))
      (node (ref "U1") (pin "P56") (pinfunction "IO_L32N_4GCLK1_P56") (pintype "bidirectional"))
    )
    (net (code "35") (name "/R1") (class "Default")
      (node (ref "R9") (pin "1") (pinfunction "1_1") (pintype "passive"))
      (node (ref "U1") (pin "P53") (pinfunction "IO_L32N_5GCLK3_P53") (pintype "bidirectional"))
    )
    (net (code "36") (name "/RESET") (class "Default")
      (node (ref "R52") (pin "2") (pinfunction "2_2") (pintype "passive"))
      (node (ref "RESET_SW") (pin "1") (pinfunction "1_1") (pintype "passive"))
    )
    (net (code "37") (name "/RXD") (class "Default")
      (node (ref "IC3") (pin "8") (pinfunction "PD2(INT2/AIN1/RXD1)_8") (pintype "bidirectional"))
    )
    (net (code "38") (name "/SAA") (class "Default")
      (node (ref "SV1") (pin "9") (pinfunction "9_9") (pintype "passive"))
      (node (ref "U1") (pin "P52") (pinfunction "IO_L32P_5GCLK2_P52") (pintype "bidirectional"))
    )
    (net (code "39") (name "/SCART_BLANKING") (class "Default")
      (node (ref "R50") (pin "1") (pinfunction "1_1") (pintype "passive"))
      (node (ref "X2") (pin "16") (pinfunction "16_16") (pintype "passive"))
    )
    (net (code "40") (name "/SCART_BLUE") (class "Default")
      (node (ref "R31") (pin "1") (pinfunction "1_1") (pintype "passive"))
      (node (ref "R32") (pin "1") (pinfunction "1_1") (pintype "passive"))
      (node (ref "R33") (pin "1") (pinfunction "1_1") (pintype "passive"))
      (node (ref "X2") (pin "7") (pinfunction "7_7") (pintype "passive"))
    )
    (net (code "41") (name "/SCART_COMP") (class "Default")
      (node (ref "R13") (pin "1") (pinfunction "1_1") (pintype "passive"))
      (node (ref "R14") (pin "1") (pinfunction "1_1") (pintype "passive"))
      (node (ref "X2") (pin "19") (pinfunction "19_19") (pintype "passive"))
    )
    (net (code "42") (name "/SCART_GREEN") (class "Default")
      (node (ref "R26") (pin "1") (pinfunction "1_1") (pintype "passive"))
      (node (ref "R27") (pin "1") (pinfunction "1_1") (pintype "passive"))
      (node (ref "R28") (pin "1") (pinfunction "1_1") (pintype "passive"))
      (node (ref "X2") (pin "11") (pinfunction "11_11") (pintype "passive"))
    )
    (net (code "43") (name "/SCART_LEFT") (class "Default")
      (node (ref "C3") (pin "2") (pinfunction "2_2") (pintype "passive"))
      (node (ref "X2") (pin "3") (pinfunction "3_3") (pintype "passive"))
    )
    (net (code "44") (name "/SCART_MODE") (class "Default")
      (node (ref "X2") (pin "8") (pinfunction "8_8") (pintype "passive"))
    )
    (net (code "45") (name "/SCART_RED") (class "Default")
      (node (ref "R15") (pin "1") (pinfunction "1_1") (pintype "passive"))
      (node (ref "R16") (pin "1") (pinfunction "1_1") (pintype "passive"))
      (node (ref "R20") (pin "1") (pinfunction "1_1") (pintype "passive"))
      (node (ref "X2") (pin "15") (pinfunction "15_15") (pintype "passive"))
    )
    (net (code "46") (name "/SCART_RIGHT") (class "Default")
      (node (ref "C4") (pin "2") (pinfunction "2_2") (pintype "passive"))
      (node (ref "X2") (pin "1") (pinfunction "1_1") (pintype "passive"))
    )
    (net (code "47") (name "/SPI_MISO") (class "Default")
      (node (ref "IC3") (pin "17") (pinfunction "PB3(PDO/MISO/PCINT3)_17") (pintype "bidirectional"))
    )
    (net (code "48") (name "/SPI_MOSI") (class "Default")
      (node (ref "IC3") (pin "16") (pinfunction "PB2(PDI/MOSI/PCINT2)_16") (pintype "bidirectional"))
    )
    (net (code "49") (name "/SPI_SCLK") (class "Default")
      (node (ref "IC3") (pin "15") (pinfunction "PB1(SCK/PCINT1)_15") (pintype "bidirectional"))
    )
    (net (code "50") (name "/SPI_SEL") (class "Default")
      (node (ref "IC3") (pin "14") (pinfunction "PB0(SS/PCINT0)_14") (pintype "bidirectional"))
    )
    (net (code "51") (name "/TCK") (class "Default")
      (node (ref "IC1") (pin "6") (pinfunction "TCK_6") (pintype "bidirectional"))
      (node (ref "IC3") (pin "18") (pinfunction "PB4(T1/PCINT4)_18") (pintype "bidirectional"))
      (node (ref "JP3") (pin "3") (pinfunction "3_3") (pintype "passive"))
      (node (ref "R2") (pin "2") (pinfunction "2_2") (pintype "passive"))
    )
    (net (code "52") (name "/TDI_FPGA") (class "Default")
      (node (ref "IC3") (pin "20") (pinfunction "PB6(PCINT6)_20") (pintype "bidirectional"))
      (node (ref "R1") (pin "2") (pinfunction "2_2") (pintype "passive"))
    )
    (net (code "53") (name "/TDO_EXP") (class "Default")
      (node (ref "IC3") (pin "21") (pinfunction "PB7(OC0A/OC1C/PCINT7)_21") (pintype "bidirectional"))
      (node (ref "JP3") (pin "1") (pinfunction "1_1") (pintype "passive"))
    )
    (net (code "54") (name "/TDO_PROM") (class "Default")
      (node (ref "IC1") (pin "17") (pinfunction "TDO_17") (pintype "bidirectional"))
      (node (ref "IC3") (pin "22") (pinfunction "PC7(ICP1/INT4/CLKO)_22") (pintype "bidirectional"))
      (node (ref "JP3") (pin "2") (pinfunction "2_2") (pintype "passive"))
    )
    (net (code "55") (name "/TMS") (class "Default")
      (node (ref "IC1") (pin "5") (pinfunction "TMS_5") (pintype "bidirectional"))
      (node (ref "IC3") (pin "19") (pinfunction "PB5(PCINT5)_19") (pintype "bidirectional"))
      (node (ref "JP3") (pin "5") (pinfunction "5_5") (pintype "passive"))
      (node (ref "R3") (pin "2") (pinfunction "2_2") (pintype "passive"))
    )
    (net (code "56") (name "/TXD") (class "Default")
      (node (ref "IC3") (pin "9") (pinfunction "PD3(INT3/TXD1)_9") (pintype "bidirectional"))
    )
    (net (code "57") (name "/VCC") (class "Default")
      (node (ref "C10") (pin "1") (pinfunction "1_1") (pintype "passive"))
      (node (ref "C11") (pin "1") (pinfunction "1_1") (pintype "passive"))
      (node (ref "C12") (pin "1") (pinfunction "1_1") (pintype "passive"))
      (node (ref "C13") (pin "1") (pinfunction "1_1") (pintype "passive"))
      (node (ref "C14") (pin "1") (pinfunction "1_1") (pintype "passive"))
      (node (ref "C15") (pin "1") (pinfunction "1_1") (pintype "passive"))
      (node (ref "C16") (pin "1") (pinfunction "1_1") (pintype "passive"))
      (node (ref "C17") (pin "1") (pinfunction "1_1") (pintype "passive"))
      (node (ref "C26") (pin "1") (pinfunction "1_1") (pintype "passive"))
      (node (ref "C27") (pin "1") (pinfunction "1_1") (pintype "passive"))
      (node (ref "C28") (pin "1") (pinfunction "1_1") (pintype "passive"))
      (node (ref "C29") (pin "1") (pinfunction "1_1") (pintype "passive"))
      (node (ref "C30") (pin "1") (pinfunction "1_1") (pintype "passive"))
      (node (ref "C31") (pin "1") (pinfunction "1_1") (pintype "passive"))
      (node (ref "C32") (pin "1") (pinfunction "1_1") (pintype "passive"))
      (node (ref "C34") (pin "1") (pinfunction "1_1") (pintype "passive"))
      (node (ref "C6") (pin "1") (pinfunction "1_1") (pintype "passive"))
      (node (ref "C7") (pin "1") (pinfunction "1_1") (pintype "passive"))
      (node (ref "C8") (pin "1") (pinfunction "1_1") (pintype "passive"))
      (node (ref "C9") (pin "1") (pinfunction "1_1") (pintype "passive"))
      (node (ref "IC1") (pin "18") (pinfunction "VCCINT_18") (pintype "bidirectional"))
      (node (ref "IC1") (pin "19") (pinfunction "VCCO_19") (pintype "bidirectional"))
      (node (ref "IC1") (pin "20") (pinfunction "VCCJ_20") (pintype "bidirectional"))
      (node (ref "IC2") (pin "8") (pinfunction "VCC_8") (pintype "power_in"))
      (node (ref "IC3") (pin "31") (pinfunction "UVCC_31") (pintype "bidirectional"))
      (node (ref "IC3") (pin "32") (pinfunction "AVCC_32") (pintype "bidirectional"))
      (node (ref "IC3") (pin "4") (pinfunction "VCC_4") (pintype "bidirectional"))
      (node (ref "JP1") (pin "2") (pinfunction "2_2") (pintype "passive"))
      (node (ref "JP3") (pin "4") (pinfunction "4_4") (pintype "passive"))
      (node (ref "Q5") (pin "3") (pinfunction "C_3") (pintype "passive"))
      (node (ref "Q6") (pin "3") (pinfunction "C_3") (pintype "passive"))
      (node (ref "Q7") (pin "3") (pinfunction "C_3") (pintype "passive"))
      (node (ref "Q8") (pin "3") (pinfunction "C_3") (pintype "passive"))
      (node (ref "R22") (pin "1") (pinfunction "1_1") (pintype "passive"))
      (node (ref "R35") (pin "2") (pinfunction "2_2") (pintype "passive"))
      (node (ref "R36") (pin "2") (pinfunction "2_2") (pintype "passive"))
      (node (ref "R37") (pin "2") (pinfunction "2_2") (pintype "passive"))
      (node (ref "R38") (pin "2") (pinfunction "2_2") (pintype "passive"))
      (node (ref "R39") (pin "2") (pinfunction "2_2") (pintype "passive"))
      (node (ref "R4") (pin "2") (pinfunction "2_2") (pintype "passive"))
      (node (ref "R40") (pin "1") (pinfunction "1_1") (pintype "passive"))
      (node (ref "R41") (pin "1") (pinfunction "1_1") (pintype "passive"))
      (node (ref "R42") (pin "1") (pinfunction "1_1") (pintype "passive"))
      (node (ref "R43") (pin "1") (pinfunction "1_1") (pintype "passive"))
      (node (ref "R44") (pin "1") (pinfunction "1_1") (pintype "passive"))
      (node (ref "R45") (pin "1") (pinfunction "1_1") (pintype "passive"))
      (node (ref "R46") (pin "2") (pinfunction "2_2") (pintype "passive"))
      (node (ref "R52") (pin "1") (pinfunction "1_1") (pintype "passive"))
      (node (ref "R6") (pin "2") (pinfunction "2_2") (pintype "passive"))
      (node (ref "SV1") (pin "1") (pinfunction "1_1") (pintype "passive"))
      (node (ref "T1") (pin "3") (pinfunction "G_3") (pintype "passive"))
      (node (ref "T2") (pin "3") (pinfunction "C_3") (pintype "passive"))
      (node (ref "T3") (pin "3") (pinfunction "G_3") (pintype "passive"))
      (node (ref "U$2") (pin "VDD") (pinfunction "VDD_VDD") (pintype "power_in"))
      (node (ref "U$4") (pin "4") (pinfunction "VOUT1_4") (pintype "bidirectional"))
      (node (ref "U$5") (pin "2") (pinfunction "VOUT1_2") (pintype "output"))
      (node (ref "U$5") (pin "3") (pinfunction "VOUT2_3") (pintype "output"))
      (node (ref "U$5") (pin "6") (pinfunction "VOUT3_6") (pintype "output"))
      (node (ref "U$5") (pin "7") (pinfunction "VOUT4_7") (pintype "output"))
      (node (ref "U$6") (pin "P8") (pinfunction "VCC_P8") (pintype "bidirectional"))
      (node (ref "U1") (pin "P106") (pinfunction "VCCO_RIGHT2_P106") (pintype "passive"))
      (node (ref "U1") (pin "P115") (pinfunction "VCCO_TOP0_P115") (pintype "passive"))
      (node (ref "U1") (pin "P126") (pinfunction "VCCO_TOP1_P126") (pintype "passive"))
      (node (ref "U1") (pin "P138") (pinfunction "VCCO_TOP2_P138") (pintype "passive"))
      (node (ref "U1") (pin "P19") (pinfunction "VCCO_LEFT1_P19") (pintype "passive"))
      (node (ref "U1") (pin "P3") (pinfunction "VCCO_LEFT0_P3") (pintype "passive"))
      (node (ref "U1") (pin "P34") (pinfunction "VCCO_LEFT2_P34") (pintype "passive"))
      (node (ref "U1") (pin "P43") (pinfunction "VCCO_BOTTOM0_P43") (pintype "passive"))
      (node (ref "U1") (pin "P54") (pinfunction "VCCO_BOTTOM1_P54") (pintype "passive"))
      (node (ref "U1") (pin "P66") (pinfunction "VCCO_BOTTOM2_P66") (pintype "passive"))
      (node (ref "U1") (pin "P75") (pinfunction "VCCO_RIGHT0_P75") (pintype "passive"))
      (node (ref "U1") (pin "P91") (pinfunction "VCCO_RIGHT1_P91") (pintype "passive"))
    )
    (net (code "58") (name "/VCC5") (class "Default")
      (node (ref "C33") (pin "+") (pinfunction "+_+") (pintype "passive"))
      (node (ref "C35") (pin "+") (pinfunction "+_+") (pintype "passive"))
      (node (ref "C36") (pin "+") (pinfunction "+_+") (pintype "passive"))
      (node (ref "R5") (pin "2") (pinfunction "2_2") (pintype "passive"))
      (node (ref "R7") (pin "2") (pinfunction "2_2") (pintype "passive"))
      (node (ref "REG1.2") (pin "3") (pinfunction "VCC_3") (pintype "bidirectional"))
      (node (ref "REG2.5") (pin "3") (pinfunction "VCC_3") (pintype "bidirectional"))
      (node (ref "U$4") (pin "3") (pinfunction "VCC_3") (pintype "bidirectional"))
      (node (ref "U$5") (pin "4") (pinfunction "VCC_4") (pintype "bidirectional"))
      (node (ref "X3") (pin "5") (pinfunction "5_5") (pintype "passive"))
      (node (ref "X7") (pin "2") (pinfunction "2_2") (pintype "power_in"))
    )
    (net (code "59") (name "/VCCAUX") (class "Default")
      (node (ref "C18") (pin "1") (pinfunction "1_1") (pintype "passive"))
      (node (ref "C19") (pin "1") (pinfunction "1_1") (pintype "passive"))
      (node (ref "C20") (pin "1") (pinfunction "1_1") (pintype "passive"))
      (node (ref "C21") (pin "1") (pinfunction "1_1") (pintype "passive"))
      (node (ref "R50") (pin "2") (pinfunction "2_2") (pintype "passive"))
      (node (ref "REG2.5") (pin "4") (pinfunction "VOUT1_4") (pintype "bidirectional"))
      (node (ref "U1") (pin "P120") (pinfunction "VCCAUX2_P120") (pintype "passive"))
      (node (ref "U1") (pin "P134") (pinfunction "VCCAUX3_P134") (pintype "passive"))
      (node (ref "U1") (pin "P48") (pinfunction "VCCAUX0_P48") (pintype "passive"))
      (node (ref "U1") (pin "P62") (pinfunction "VCCAUX1_P62") (pintype "passive"))
    )
    (net (code "60") (name "/VCCINT") (class "Default")
      (node (ref "C22") (pin "1") (pinfunction "1_1") (pintype "passive"))
      (node (ref "C23") (pin "1") (pinfunction "1_1") (pintype "passive"))
      (node (ref "C24") (pin "1") (pinfunction "1_1") (pintype "passive"))
      (node (ref "C25") (pin "1") (pinfunction "1_1") (pintype "passive"))
      (node (ref "REG1.2") (pin "4") (pinfunction "VOUT1_4") (pintype "bidirectional"))
      (node (ref "U1") (pin "P121") (pinfunction "VCCINT2_P121") (pintype "passive"))
      (node (ref "U1") (pin "P133") (pinfunction "VCCINT3_P133") (pintype "passive"))
      (node (ref "U1") (pin "P49") (pinfunction "VCCINT0_P49") (pintype "passive"))
      (node (ref "U1") (pin "P61") (pinfunction "VCCINT1_P61") (pintype "passive"))
    )
    (net (code "61") (name "/VCC_B3") (class "Default")
      (node (ref "R11") (pin "2") (pinfunction "2_2") (pintype "passive"))
    )
    (net (code "65") (name "/XXCSYNC") (class "Default")
      (node (ref "U1") (pin "P137") (pinfunction "IO_L27N_0_P137") (pintype "bidirectional"))
    )
    (net (code "67") (name "/XXZXZ") (class "Default")
      (node (ref "SV1") (pin "11") (pinfunction "11_11") (pintype "passive"))
      (node (ref "U1") (pin "P57") (pinfunction "IO_L31P_4DOUTBUSY_P57") (pintype "bidirectional"))
    )
    (net (code "68") (name "GND") (class "Default")
      (node (ref "C1") (pin "1") (pinfunction "1_1") (pintype "passive"))
      (node (ref "C10") (pin "2") (pinfunction "2_2") (pintype "passive"))
      (node (ref "C11") (pin "2") (pinfunction "2_2") (pintype "passive"))
      (node (ref "C12") (pin "2") (pinfunction "2_2") (pintype "passive"))
      (node (ref "C13") (pin "2") (pinfunction "2_2") (pintype "passive"))
      (node (ref "C14") (pin "2") (pinfunction "2_2") (pintype "passive"))
      (node (ref "C15") (pin "2") (pinfunction "2_2") (pintype "passive"))
      (node (ref "C16") (pin "2") (pinfunction "2_2") (pintype "passive"))
      (node (ref "C17") (pin "2") (pinfunction "2_2") (pintype "passive"))
      (node (ref "C18") (pin "2") (pinfunction "2_2") (pintype "passive"))
      (node (ref "C19") (pin "2") (pinfunction "2_2") (pintype "passive"))
      (node (ref "C20") (pin "2") (pinfunction "2_2") (pintype "passive"))
      (node (ref "C21") (pin "2") (pinfunction "2_2") (pintype "passive"))
      (node (ref "C22") (pin "2") (pinfunction "2_2") (pintype "passive"))
      (node (ref "C23") (pin "2") (pinfunction "2_2") (pintype "passive"))
      (node (ref "C24") (pin "2") (pinfunction "2_2") (pintype "passive"))
      (node (ref "C25") (pin "2") (pinfunction "2_2") (pintype "passive"))
      (node (ref "C26") (pin "2") (pinfunction "2_2") (pintype "passive"))
      (node (ref "C27") (pin "2") (pinfunction "2_2") (pintype "passive"))
      (node (ref "C28") (pin "2") (pinfunction "2_2") (pintype "passive"))
      (node (ref "C29") (pin "2") (pinfunction "2_2") (pintype "passive"))
      (node (ref "C30") (pin "2") (pinfunction "2_2") (pintype "passive"))
      (node (ref "C31") (pin "2") (pinfunction "2_2") (pintype "passive"))
      (node (ref "C32") (pin "2") (pinfunction "2_2") (pintype "passive"))
      (node (ref "C33") (pin "-") (pinfunction "-_-") (pintype "passive"))
      (node (ref "C34") (pin "2") (pinfunction "2_2") (pintype "passive"))
      (node (ref "C35") (pin "-") (pinfunction "-_-") (pintype "passive"))
      (node (ref "C36") (pin "-") (pinfunction "-_-") (pintype "passive"))
      (node (ref "C5") (pin "1") (pinfunction "1_1") (pintype "passive"))
      (node (ref "C6") (pin "2") (pinfunction "2_2") (pintype "passive"))
      (node (ref "C7") (pin "2") (pinfunction "2_2") (pintype "passive"))
      (node (ref "C8") (pin "2") (pinfunction "2_2") (pintype "passive"))
      (node (ref "C9") (pin "2") (pinfunction "2_2") (pintype "passive"))
      (node (ref "IC1") (pin "11") (pinfunction "GND_11") (pintype "bidirectional"))
      (node (ref "IC2") (pin "4") (pinfunction "GND_4") (pintype "power_in"))
      (node (ref "IC3") (pin "3") (pinfunction "GND_3") (pintype "bidirectional"))
      (node (ref "JP1") (pin "1") (pinfunction "1_1") (pintype "passive"))
      (node (ref "JP3") (pin "6") (pinfunction "6_6") (pintype "passive"))
      (node (ref "R12") (pin "1") (pinfunction "1_1") (pintype "passive"))
      (node (ref "R17") (pin "1") (pinfunction "1_1") (pintype "passive"))
      (node (ref "R19") (pin "1") (pinfunction "1_1") (pintype "passive"))
      (node (ref "R21") (pin "1") (pinfunction "1_1") (pintype "passive"))
      (node (ref "REG1.2") (pin "1") (pinfunction "GND_1") (pintype "bidirectional"))
      (node (ref "REG2.5") (pin "1") (pinfunction "GND_1") (pintype "bidirectional"))
      (node (ref "RESET_SW") (pin "2") (pinfunction "2_2") (pintype "passive"))
      (node (ref "SV1") (pin "12") (pinfunction "12_12") (pintype "passive"))
      (node (ref "SV1") (pin "2") (pinfunction "2_2") (pintype "passive"))
      (node (ref "U$2") (pin "GND") (pinfunction "GND_GND") (pintype "power_in"))
      (node (ref "U$4") (pin "1") (pinfunction "GND_1") (pintype "bidirectional"))
      (node (ref "U$5") (pin "1") (pinfunction "GND_1") (pintype "bidirectional"))
      (node (ref "U$6") (pin "P24") (pinfunction "VSS_P24") (pintype "bidirectional"))
      (node (ref "U$6") (pin "P30") (pinfunction "CE_P30") (pintype "bidirectional"))
      (node (ref "U1") (pin "P101") (pinfunction "GND11_P101") (pintype "passive"))
      (node (ref "U1") (pin "P114") (pinfunction "GND12_P114") (pintype "passive"))
      (node (ref "U1") (pin "P117") (pinfunction "GND13_P117") (pintype "passive"))
      (node (ref "U1") (pin "P136") (pinfunction "GND14_P136") (pintype "passive"))
      (node (ref "U1") (pin "P139") (pinfunction "GND15_P139") (pintype "passive"))
      (node (ref "U1") (pin "P16") (pinfunction "GND1_P16") (pintype "passive"))
      (node (ref "U1") (pin "P22") (pinfunction "GND2_P22") (pintype "passive"))
      (node (ref "U1") (pin "P29") (pinfunction "GND3_P29") (pintype "passive"))
      (node (ref "U1") (pin "P37") (pinfunction "M1_P37") (pintype "bidirectional"))
      (node (ref "U1") (pin "P38") (pinfunction "M0_P38") (pintype "bidirectional"))
      (node (ref "U1") (pin "P39") (pinfunction "M2_P39") (pintype "bidirectional"))
      (node (ref "U1") (pin "P42") (pinfunction "GND4_P42") (pintype "passive"))
      (node (ref "U1") (pin "P45") (pinfunction "GND5_P45") (pintype "passive"))
      (node (ref "U1") (pin "P64") (pinfunction "GND6_P64") (pintype "passive"))
      (node (ref "U1") (pin "P67") (pinfunction "GND7_P67") (pintype "passive"))
      (node (ref "U1") (pin "P81") (pinfunction "GND8_P81") (pintype "passive"))
      (node (ref "U1") (pin "P88") (pinfunction "GND9_P88") (pintype "passive"))
      (node (ref "U1") (pin "P9") (pinfunction "GND0_P9") (pintype "passive"))
      (node (ref "U1") (pin "P94") (pinfunction "GND10_P94") (pintype "passive"))
      (node (ref "X1") (pin "3") (pinfunction "2_3") (pintype "passive"))
      (node (ref "X2") (pin "13") (pinfunction "13_13") (pintype "passive"))
      (node (ref "X2") (pin "14") (pinfunction "14_14") (pintype "passive"))
      (node (ref "X2") (pin "17") (pinfunction "17_17") (pintype "passive"))
      (node (ref "X2") (pin "18") (pinfunction "18_18") (pintype "passive"))
      (node (ref "X2") (pin "21") (pinfunction "21_21") (pintype "passive"))
      (node (ref "X2") (pin "4") (pinfunction "4_4") (pintype "passive"))
      (node (ref "X2") (pin "5") (pinfunction "5_5") (pintype "passive"))
      (node (ref "X2") (pin "9") (pinfunction "9_9") (pintype "passive"))
      (node (ref "X3") (pin "3") (pinfunction "3_3") (pintype "passive"))
      (node (ref "X3") (pin "SH1") (pinfunction "PE1_SH1") (pintype "power_in"))
      (node (ref "X3") (pin "SH2") (pinfunction "PE2_SH2") (pintype "power_in"))
      (node (ref "X3") (pin "SH3") (pinfunction "PE3_SH3") (pintype "power_in"))
      (node (ref "X4") (pin "8") (pinfunction "F_8") (pintype "passive"))
      (node (ref "X4") (pin "G1") (pinfunction "G1_G1") (pintype "passive"))
      (node (ref "X5") (pin "8") (pinfunction "F_8") (pintype "passive"))
      (node (ref "X5") (pin "G1") (pinfunction "G1_G1") (pintype "passive"))
      (node (ref "X7") (pin "3") (pinfunction "3_3") (pintype "power_in"))
    )
    (net (code "69") (name "Net-(C1-Pad2)") (class "Default")
      (node (ref "C1") (pin "2") (pinfunction "2_2") (pintype "passive"))
      (node (ref "R23") (pin "2") (pinfunction "2_2") (pintype "passive"))
      (node (ref "R48") (pin "1") (pinfunction "1_1") (pintype "passive"))
    )
    (net (code "70") (name "Net-(C2-Pad1)") (class "Default")
      (node (ref "C2") (pin "1") (pinfunction "1_1") (pintype "passive"))
      (node (ref "R17") (pin "2") (pinfunction "2_2") (pintype "passive"))
      (node (ref "X1") (pin "1") (pinfunction "1_1") (pintype "passive"))
    )
    (net (code "71") (name "Net-(C3-Pad1)") (class "Default")
      (node (ref "C3") (pin "1") (pinfunction "1_1") (pintype "passive"))
      (node (ref "R48") (pin "2") (pinfunction "2_2") (pintype "passive"))
    )
    (net (code "72") (name "Net-(C4-Pad1)") (class "Default")
      (node (ref "C4") (pin "1") (pinfunction "1_1") (pintype "passive"))
      (node (ref "R49") (pin "2") (pinfunction "2_2") (pintype "passive"))
    )
    (net (code "73") (name "Net-(C5-Pad2)") (class "Default")
      (node (ref "C5") (pin "2") (pinfunction "2_2") (pintype "passive"))
      (node (ref "R34") (pin "2") (pinfunction "2_2") (pintype "passive"))
      (node (ref "R49") (pin "1") (pinfunction "1_1") (pintype "passive"))
    )
    (net (code "74") (name "Net-(IC1-CLK)") (class "Default")
      (node (ref "IC1") (pin "3") (pinfunction "CLK_3") (pintype "bidirectional"))
      (node (ref "U1") (pin "P72") (pinfunction "CCLK_P72") (pintype "bidirectional"))
    )
    (net (code "75") (name "Net-(IC1-TDI)") (class "Default")
      (node (ref "IC1") (pin "4") (pinfunction "TDI_4") (pintype "bidirectional"))
      (node (ref "U1") (pin "P109") (pinfunction "TDO_P109") (pintype "bidirectional"))
    )
    (net (code "76") (name "Net-(IC1-{slash}CE)") (class "Default")
      (node (ref "IC1") (pin "10") (pinfunction "/CE_10") (pintype "bidirectional"))
      (node (ref "U1") (pin "P71") (pinfunction "DONE_P71") (pintype "bidirectional"))
    )
    (net (code "77") (name "Net-(IC1-{slash}CF)") (class "Default")
      (node (ref "IC1") (pin "7") (pinfunction "/CF_7") (pintype "bidirectional"))
      (node (ref "U1") (pin "P143") (pinfunction "PROG_B_P143") (pintype "bidirectional"))
    )
    (net (code "78") (name "Net-(IC3-D+)") (class "Default")
      (node (ref "IC3") (pin "29") (pinfunction "D+_29") (pintype "bidirectional"))
      (node (ref "R54") (pin "2") (pinfunction "2_2") (pintype "passive"))
    )
    (net (code "79") (name "Net-(IC3-D-)") (class "Default")
      (node (ref "IC3") (pin "30") (pinfunction "D-_30") (pintype "bidirectional"))
      (node (ref "R53") (pin "2") (pinfunction "2_2") (pintype "passive"))
    )
    (net (code "80") (name "Net-(IC3-UGND)") (class "Default")
      (node (ref "IC3") (pin "28") (pinfunction "UGND_28") (pintype "bidirectional"))
      (node (ref "X6") (pin "4") (pinfunction "4_4") (pintype "passive"))
    )
    (net (code "81") (name "Net-(Q5-B)") (class "Default")
      (node (ref "Q5") (pin "1") (pinfunction "B_1") (pintype "passive"))
      (node (ref "R8") (pin "2") (pinfunction "2_2") (pintype "passive"))
    )
    (net (code "82") (name "Net-(Q5-E)") (class "Default")
      (node (ref "Q5") (pin "2") (pinfunction "E_2") (pintype "passive"))
      (node (ref "R13") (pin "2") (pinfunction "2_2") (pintype "passive"))
      (node (ref "R14") (pin "2") (pinfunction "2_2") (pintype "passive"))
    )
    (net (code "83") (name "Net-(Q6-B)") (class "Default")
      (node (ref "Q6") (pin "1") (pinfunction "B_1") (pintype "passive"))
      (node (ref "R10") (pin "2") (pinfunction "2_2") (pintype "passive"))
      (node (ref "R9") (pin "2") (pinfunction "2_2") (pintype "passive"))
    )
    (net (code "84") (name "Net-(Q6-E)") (class "Default")
      (node (ref "Q6") (pin "2") (pinfunction "E_2") (pintype "passive"))
      (node (ref "R15") (pin "2") (pinfunction "2_2") (pintype "passive"))
      (node (ref "R16") (pin "2") (pinfunction "2_2") (pintype "passive"))
      (node (ref "R20") (pin "2") (pinfunction "2_2") (pintype "passive"))
    )
    (net (code "85") (name "Net-(Q7-B)") (class "Default")
      (node (ref "Q7") (pin "1") (pinfunction "B_1") (pintype "passive"))
      (node (ref "R29") (pin "2") (pinfunction "2_2") (pintype "passive"))
      (node (ref "R30") (pin "2") (pinfunction "2_2") (pintype "passive"))
    )
    (net (code "86") (name "Net-(Q7-E)") (class "Default")
      (node (ref "Q7") (pin "2") (pinfunction "E_2") (pintype "passive"))
      (node (ref "R31") (pin "2") (pinfunction "2_2") (pintype "passive"))
      (node (ref "R32") (pin "2") (pinfunction "2_2") (pintype "passive"))
      (node (ref "R33") (pin "2") (pinfunction "2_2") (pintype "passive"))
    )
    (net (code "87") (name "Net-(Q8-B)") (class "Default")
      (node (ref "Q8") (pin "1") (pinfunction "B_1") (pintype "passive"))
      (node (ref "R24") (pin "2") (pinfunction "2_2") (pintype "passive"))
      (node (ref "R25") (pin "2") (pinfunction "2_2") (pintype "passive"))
    )
    (net (code "88") (name "Net-(Q8-E)") (class "Default")
      (node (ref "Q8") (pin "2") (pinfunction "E_2") (pintype "passive"))
      (node (ref "R26") (pin "2") (pinfunction "2_2") (pintype "passive"))
      (node (ref "R27") (pin "2") (pinfunction "2_2") (pintype "passive"))
      (node (ref "R28") (pin "2") (pinfunction "2_2") (pintype "passive"))
    )
    (net (code "89") (name "Net-(R18-Pad2)") (class "Default")
      (node (ref "R18") (pin "2") (pinfunction "2_2") (pintype "passive"))
      (node (ref "R22") (pin "2") (pinfunction "2_2") (pintype "passive"))
    )
    (net (code "90") (name "Net-(R53-Pad1)") (class "Default")
      (node (ref "R53") (pin "1") (pinfunction "1_1") (pintype "passive"))
      (node (ref "X6") (pin "2") (pinfunction "2_2") (pintype "passive"))
    )
    (net (code "91") (name "Net-(R54-Pad1)") (class "Default")
      (node (ref "R54") (pin "1") (pinfunction "1_1") (pintype "passive"))
      (node (ref "X6") (pin "3") (pinfunction "3_3") (pintype "passive"))
    )
    (net (code "92") (name "Net-(T2-B)") (class "Default")
      (node (ref "C2") (pin "2") (pinfunction "2_2") (pintype "passive"))
      (node (ref "R18") (pin "1") (pinfunction "1_1") (pintype "passive"))
      (node (ref "R19") (pin "2") (pinfunction "2_2") (pintype "passive"))
      (node (ref "T2") (pin "1") (pinfunction "B_1") (pintype "passive"))
    )
    (net (code "93") (name "Net-(U$6-A0)") (class "Default")
      (node (ref "U$6") (pin "P20") (pinfunction "A0_P20") (pintype "bidirectional"))
      (node (ref "U1") (pin "P24") (pinfunction "IO_L24N_6VREF_6_P24") (pintype "bidirectional"))
    )
    (net (code "94") (name "Net-(U$6-A1)") (class "Default")
      (node (ref "U$6") (pin "P19") (pinfunction "A1_P19") (pintype "bidirectional"))
      (node (ref "U1") (pin "P23") (pinfunction "IO_L24P_6_P23") (pintype "bidirectional"))
    )
    (net (code "95") (name "Net-(U$6-A2)") (class "Default")
      (node (ref "U$6") (pin "P18") (pinfunction "A2_P18") (pintype "bidirectional"))
      (node (ref "U1") (pin "P21") (pinfunction "IO_L40N_6_P21") (pintype "bidirectional"))
    )
    (net (code "96") (name "Net-(U$6-A3)") (class "Default")
      (node (ref "U$6") (pin "P17") (pinfunction "A3_P17") (pintype "bidirectional"))
      (node (ref "U1") (pin "P20") (pinfunction "IO_L40P_6VREF_6_P20") (pintype "bidirectional"))
    )
    (net (code "97") (name "Net-(U$6-A4)") (class "Default")
      (node (ref "U$6") (pin "P16") (pinfunction "A4_P16") (pintype "bidirectional"))
      (node (ref "U1") (pin "P18") (pinfunction "IO_L40N_7VREF_7_P18") (pintype "bidirectional"))
    )
    (net (code "98") (name "Net-(U$6-A5)") (class "Default")
      (node (ref "U$6") (pin "P15") (pinfunction "A5_P15") (pintype "bidirectional"))
      (node (ref "U1") (pin "P17") (pinfunction "IO_L40P_7_P17") (pintype "bidirectional"))
    )
    (net (code "99") (name "Net-(U$6-A6)") (class "Default")
      (node (ref "U$6") (pin "P14") (pinfunction "A6_P14") (pintype "bidirectional"))
      (node (ref "U1") (pin "P15") (pinfunction "IO_L24N_7_P15") (pintype "bidirectional"))
    )
    (net (code "100") (name "Net-(U$6-A7)") (class "Default")
      (node (ref "U$6") (pin "P13") (pinfunction "A7_P13") (pintype "bidirectional"))
      (node (ref "U1") (pin "P14") (pinfunction "IO_L24P_7_P14") (pintype "bidirectional"))
    )
    (net (code "101") (name "Net-(U$6-A8)") (class "Default")
      (node (ref "U$6") (pin "P3") (pinfunction "A8_P3") (pintype "bidirectional"))
      (node (ref "U1") (pin "P4") (pinfunction "IOVREF_7_P4") (pintype "bidirectional"))
    )
    (net (code "102") (name "Net-(U$6-A9)") (class "Default")
      (node (ref "U$6") (pin "P2") (pinfunction "A9_P2") (pintype "bidirectional"))
      (node (ref "U1") (pin "P2") (pinfunction "IO_L01N_7VRP_7_P2") (pintype "bidirectional"))
    )
    (net (code "103") (name "Net-(U$6-A10)") (class "Default")
      (node (ref "U$6") (pin "P31") (pinfunction "A10_P31") (pintype "bidirectional"))
      (node (ref "U1") (pin "P35") (pinfunction "IO_L01P_6VRN_6_P35") (pintype "bidirectional"))
    )
    (net (code "104") (name "Net-(U$6-A11)") (class "Default")
      (node (ref "U$6") (pin "P1") (pinfunction "A11_P1") (pintype "bidirectional"))
      (node (ref "U1") (pin "P1") (pinfunction "IO_L01P_7VRN_7_P1") (pintype "bidirectional"))
    )
    (net (code "105") (name "Net-(U$6-A12)") (class "Default")
      (node (ref "U$6") (pin "P12") (pinfunction "A12_P12") (pintype "bidirectional"))
      (node (ref "U1") (pin "P13") (pinfunction "IO_L23N_7_P13") (pintype "bidirectional"))
    )
    (net (code "106") (name "Net-(U$6-A13)") (class "Default")
      (node (ref "U$6") (pin "P4") (pinfunction "A13_P4") (pintype "bidirectional"))
      (node (ref "U1") (pin "P5") (pinfunction "IO_L20P_7_P5") (pintype "bidirectional"))
    )
    (net (code "107") (name "Net-(U$6-A14)") (class "Default")
      (node (ref "U$6") (pin "P11") (pinfunction "A14_P11") (pintype "bidirectional"))
      (node (ref "U1") (pin "P12") (pinfunction "IO_L23P_7_P12") (pintype "bidirectional"))
    )
    (net (code "108") (name "Net-(U$6-A15)") (class "Default")
      (node (ref "U$6") (pin "P7") (pinfunction "A15_P7") (pintype "bidirectional"))
      (node (ref "U1") (pin "P8") (pinfunction "IO_L21N_7_P8") (pintype "bidirectional"))
    )
    (net (code "109") (name "Net-(U$6-A16)") (class "Default")
      (node (ref "U$6") (pin "P10") (pinfunction "A16_P10") (pintype "bidirectional"))
      (node (ref "U1") (pin "P11") (pinfunction "IO_L22N_7_P11") (pintype "bidirectional"))
    )
    (net (code "110") (name "Net-(U$6-A17)") (class "Default")
      (node (ref "U$6") (pin "P6") (pinfunction "A17_P6") (pintype "bidirectional"))
      (node (ref "U1") (pin "P7") (pinfunction "IO_L21P_7_P7") (pintype "bidirectional"))
    )
    (net (code "111") (name "Net-(U$6-A18)") (class "Default")
      (node (ref "U$6") (pin "P9") (pinfunction "A18_P9") (pintype "bidirectional"))
      (node (ref "U1") (pin "P10") (pinfunction "IO_L22P_7_P10") (pintype "bidirectional"))
    )
    (net (code "112") (name "Net-(U$6-DQ0)") (class "Default")
      (node (ref "U$6") (pin "P21") (pinfunction "DQ0_P21") (pintype "bidirectional"))
      (node (ref "U1") (pin "P25") (pinfunction "IO_L23P_6_P25") (pintype "bidirectional"))
    )
    (net (code "113") (name "Net-(U$6-DQ1)") (class "Default")
      (node (ref "U$6") (pin "P22") (pinfunction "DQ1_P22") (pintype "bidirectional"))
      (node (ref "U1") (pin "P26") (pinfunction "IO_L23N_6_P26") (pintype "bidirectional"))
    )
    (net (code "114") (name "Net-(U$6-DQ2)") (class "Default")
      (node (ref "U$6") (pin "P23") (pinfunction "DQ2_P23") (pintype "bidirectional"))
      (node (ref "U1") (pin "P27") (pinfunction "IO_L22P_6_P27") (pintype "bidirectional"))
    )
    (net (code "115") (name "Net-(U$6-DQ3)") (class "Default")
      (node (ref "U$6") (pin "P25") (pinfunction "DQ3_P25") (pintype "bidirectional"))
      (node (ref "U1") (pin "P28") (pinfunction "IO_L22N_6_P28") (pintype "bidirectional"))
    )
    (net (code "116") (name "Net-(U$6-DQ4)") (class "Default")
      (node (ref "U$6") (pin "P26") (pinfunction "DQ4_P26") (pintype "bidirectional"))
      (node (ref "U1") (pin "P30") (pinfunction "IO_L21P_6_P30") (pintype "bidirectional"))
    )
    (net (code "117") (name "Net-(U$6-DQ5)") (class "Default")
      (node (ref "U$6") (pin "P27") (pinfunction "DQ5_P27") (pintype "bidirectional"))
      (node (ref "U1") (pin "P31") (pinfunction "IO_L21N_6_P31") (pintype "bidirectional"))
    )
    (net (code "118") (name "Net-(U$6-DQ6)") (class "Default")
      (node (ref "U$6") (pin "P28") (pinfunction "DQ6_P28") (pintype "bidirectional"))
      (node (ref "U1") (pin "P32") (pinfunction "IO_L20P_6_P32") (pintype "bidirectional"))
    )
    (net (code "119") (name "Net-(U$6-DQ7)") (class "Default")
      (node (ref "U$6") (pin "P29") (pinfunction "DQ7_P29") (pintype "bidirectional"))
      (node (ref "U1") (pin "P33") (pinfunction "IO_L20N_6_P33") (pintype "bidirectional"))
    )
    (net (code "120") (name "Net-(U$6-OE)") (class "Default")
      (node (ref "U$6") (pin "P32") (pinfunction "OE_P32") (pintype "bidirectional"))
      (node (ref "U1") (pin "P36") (pinfunction "IO_L01N_6VRP_6_P36") (pintype "bidirectional"))
    )
    (net (code "121") (name "Net-(U$6-WE)") (class "Default")
      (node (ref "U$6") (pin "P5") (pinfunction "WE_P5") (pintype "bidirectional"))
      (node (ref "U1") (pin "P6") (pinfunction "IO_L20N_7_P6") (pintype "bidirectional"))
    )
    (net (code "122") (name "Net-(U1G-IO_L32P_4GCLK0)") (class "Default")
      (node (ref "SV1") (pin "10") (pinfunction "10_10") (pintype "passive"))
      (node (ref "U1") (pin "P55") (pinfunction "IO_L32P_4GCLK0_P55") (pintype "bidirectional"))
    )
    (net (code "123") (name "Net-(U1N-TCK)") (class "Default")
      (node (ref "R2") (pin "1") (pinfunction "1_1") (pintype "passive"))
      (node (ref "U1") (pin "P110") (pinfunction "TCK_P110") (pintype "bidirectional"))
    )
    (net (code "124") (name "Net-(U1N-TDI)") (class "Default")
      (node (ref "R1") (pin "1") (pinfunction "1_1") (pintype "passive"))
      (node (ref "U1") (pin "P144") (pinfunction "TDI_P144") (pintype "bidirectional"))
    )
    (net (code "125") (name "Net-(U1N-TMS)") (class "Default")
      (node (ref "R3") (pin "1") (pinfunction "1_1") (pintype "passive"))
      (node (ref "U1") (pin "P111") (pinfunction "TMS_P111") (pintype "bidirectional"))
    )
    (net (code "126") (name "Net-(X4A-F)") (class "Default")
      (node (ref "R40") (pin "2") (pinfunction "2_2") (pintype "passive"))
      (node (ref "X4") (pin "1") (pinfunction "F_1") (pintype "passive"))
    )
    (net (code "127") (name "Net-(X4B-F)") (class "Default")
      (node (ref "R41") (pin "2") (pinfunction "2_2") (pintype "passive"))
      (node (ref "X4") (pin "2") (pinfunction "F_2") (pintype "passive"))
    )
    (net (code "128") (name "Net-(X4C-F)") (class "Default")
      (node (ref "R42") (pin "2") (pinfunction "2_2") (pintype "passive"))
      (node (ref "X4") (pin "3") (pinfunction "F_3") (pintype "passive"))
    )
    (net (code "129") (name "Net-(X4D-F)") (class "Default")
      (node (ref "R43") (pin "2") (pinfunction "2_2") (pintype "passive"))
      (node (ref "X4") (pin "4") (pinfunction "F_4") (pintype "passive"))
    )
    (net (code "130") (name "Net-(X4F-F)") (class "Default")
      (node (ref "R44") (pin "2") (pinfunction "2_2") (pintype "passive"))
      (node (ref "X4") (pin "6") (pinfunction "F_6") (pintype "passive"))
    )
    (net (code "131") (name "Net-(X4G-F)") (class "Default")
      (node (ref "R45") (pin "2") (pinfunction "2_2") (pintype "passive"))
      (node (ref "X4") (pin "7") (pinfunction "F_7") (pintype "passive"))
    )
    (net (code "132") (name "Net-(X5A-F)") (class "Default")
      (node (ref "R46") (pin "1") (pinfunction "1_1") (pintype "passive"))
      (node (ref "X5") (pin "1") (pinfunction "F_1") (pintype "passive"))
    )
    (net (code "133") (name "Net-(X5B-F)") (class "Default")
      (node (ref "R39") (pin "1") (pinfunction "1_1") (pintype "passive"))
      (node (ref "X5") (pin "2") (pinfunction "F_2") (pintype "passive"))
    )
    (net (code "134") (name "Net-(X5C-F)") (class "Default")
      (node (ref "R38") (pin "1") (pinfunction "1_1") (pintype "passive"))
      (node (ref "X5") (pin "3") (pinfunction "F_3") (pintype "passive"))
    )
    (net (code "135") (name "Net-(X5D-F)") (class "Default")
      (node (ref "R37") (pin "1") (pinfunction "1_1") (pintype "passive"))
      (node (ref "X5") (pin "4") (pinfunction "F_4") (pintype "passive"))
    )
    (net (code "136") (name "Net-(X5F-F)") (class "Default")
      (node (ref "R36") (pin "1") (pinfunction "1_1") (pintype "passive"))
      (node (ref "X5") (pin "6") (pinfunction "F_6") (pintype "passive"))
    )
    (net (code "137") (name "Net-(X5G-F)") (class "Default")
      (node (ref "R35") (pin "1") (pinfunction "1_1") (pintype "passive"))
      (node (ref "X5") (pin "7") (pinfunction "F_7") (pintype "passive"))
    )
    (net (code "138") (name "unconnected-(IC1-NC.1-Pad2)") (class "Default")
      (node (ref "IC1") (pin "2") (pinfunction "NC.1_2") (pintype "bidirectional"))
    )
    (net (code "139") (name "unconnected-(IC1-NC.2-Pad9)") (class "Default")
      (node (ref "IC1") (pin "9") (pinfunction "NC.2_9") (pintype "bidirectional"))
    )
    (net (code "140") (name "unconnected-(IC1-NC.3-Pad12)") (class "Default")
      (node (ref "IC1") (pin "12") (pinfunction "NC.3_12") (pintype "bidirectional"))
    )
    (net (code "141") (name "unconnected-(IC1-NC.4-Pad14)") (class "Default")
      (node (ref "IC1") (pin "14") (pinfunction "NC.4_14") (pintype "bidirectional"))
    )
    (net (code "142") (name "unconnected-(IC1-NC.5-Pad15)") (class "Default")
      (node (ref "IC1") (pin "15") (pinfunction "NC.5_15") (pintype "bidirectional"))
    )
    (net (code "143") (name "unconnected-(IC1-NC.6-Pad16)") (class "Default")
      (node (ref "IC1") (pin "16") (pinfunction "NC.6_16") (pintype "bidirectional"))
    )
    (net (code "144") (name "unconnected-(IC1-{slash}CEO-Pad13)") (class "Default")
      (node (ref "IC1") (pin "13") (pinfunction "/CEO_13") (pintype "bidirectional"))
    )
    (net (code "145") (name "unconnected-(IC3-PC2(AIN2{slash}PCIN11)-Pad5)") (class "Default")
      (node (ref "IC3") (pin "5") (pinfunction "PC2(AIN2/PCIN11)_5") (pintype "bidirectional"))
    )
    (net (code "146") (name "unconnected-(IC3-PC4(PCINT10)-Pad26)") (class "Default")
      (node (ref "IC3") (pin "26") (pinfunction "PC4(PCINT10)_26") (pintype "bidirectional"))
    )
    (net (code "147") (name "unconnected-(IC3-PC5(OC1B{slash}PCINT9)-Pad25)") (class "Default")
      (node (ref "IC3") (pin "25") (pinfunction "PC5(OC1B/PCINT9)_25") (pintype "bidirectional"))
    )
    (net (code "148") (name "unconnected-(IC3-PC6(OC1A{slash}PCINT8)-Pad23)") (class "Default")
      (node (ref "IC3") (pin "23") (pinfunction "PC6(OC1A/PCINT8)_23") (pintype "bidirectional"))
    )
    (net (code "149") (name "unconnected-(IC3-PD0(INT0{slash}OC0B)-Pad6)") (class "Default")
      (node (ref "IC3") (pin "6") (pinfunction "PD0(INT0/OC0B)_6") (pintype "bidirectional"))
    )
    (net (code "150") (name "unconnected-(IC3-PD1(INT1{slash}AIN0)-Pad7)") (class "Default")
      (node (ref "IC3") (pin "7") (pinfunction "PD1(INT1/AIN0)_7") (pintype "bidirectional"))
    )
    (net (code "151") (name "unconnected-(IC3-PD4(INT5{slash}AIN3)-Pad10)") (class "Default")
      (node (ref "IC3") (pin "10") (pinfunction "PD4(INT5/AIN3)_10") (pintype "bidirectional"))
    )
    (net (code "152") (name "unconnected-(IC3-PD5(XCK{slash}AIN4{slash}PCINT12)-Pad11)") (class "Default")
      (node (ref "IC3") (pin "11") (pinfunction "PD5(XCK/AIN4/PCINT12)_11") (pintype "bidirectional"))
    )
    (net (code "153") (name "unconnected-(IC3-PD6(INT6{slash}AIN5{slash}RTS)-Pad12)") (class "Default")
      (node (ref "IC3") (pin "12") (pinfunction "PD6(INT6/AIN5/RTS)_12") (pintype "bidirectional"))
    )
    (net (code "154") (name "unconnected-(IC3-UCAP-Pad27)") (class "Default")
      (node (ref "IC3") (pin "27") (pinfunction "UCAP_27") (pintype "bidirectional"))
    )
    (net (code "155") (name "unconnected-(IC3-XTAL1-Pad1)") (class "Default")
      (node (ref "IC3") (pin "1") (pinfunction "XTAL1_1") (pintype "bidirectional"))
    )
    (net (code "156") (name "unconnected-(IC3-XTAL2{slash}PC0-Pad2)") (class "Default")
      (node (ref "IC3") (pin "2") (pinfunction "XTAL2/PC0_2") (pintype "bidirectional"))
    )
    (net (code "157") (name "unconnected-(IC3-{slash}RESET(PC1)-Pad24)") (class "Default")
      (node (ref "IC3") (pin "24") (pinfunction "/RESET(PC1)_24") (pintype "bidirectional"))
    )
    (net (code "158") (name "unconnected-(JP1-Pad3)") (class "Default")
      (node (ref "JP1") (pin "3") (pinfunction "3_3") (pintype "passive"))
    )
    (net (code "159") (name "unconnected-(JP1-Pad4)") (class "Default")
      (node (ref "JP1") (pin "4") (pinfunction "4_4") (pintype "passive"))
    )
    (net (code "160") (name "unconnected-(JP1-Pad5)") (class "Default")
      (node (ref "JP1") (pin "5") (pinfunction "5_5") (pintype "passive"))
    )
    (net (code "161") (name "unconnected-(JP1-Pad6)") (class "Default")
      (node (ref "JP1") (pin "6") (pinfunction "6_6") (pintype "passive"))
    )
    (net (code "162") (name "unconnected-(JP1-Pad7)") (class "Default")
      (node (ref "JP1") (pin "7") (pinfunction "7_7") (pintype "passive"))
    )
    (net (code "163") (name "unconnected-(JP1-Pad8)") (class "Default")
      (node (ref "JP1") (pin "8") (pinfunction "8_8") (pintype "passive"))
    )
    (net (code "164") (name "unconnected-(JP1-Pad9)") (class "Default")
      (node (ref "JP1") (pin "9") (pinfunction "9_9") (pintype "passive"))
    )
    (net (code "165") (name "unconnected-(JP1-Pad10)") (class "Default")
      (node (ref "JP1") (pin "10") (pinfunction "10_10") (pintype "passive"))
    )
    (net (code "166") (name "unconnected-(JP1-Pad11)") (class "Default")
      (node (ref "JP1") (pin "11") (pinfunction "11_11") (pintype "passive"))
    )
    (net (code "167") (name "unconnected-(JP1-Pad12)") (class "Default")
      (node (ref "JP1") (pin "12") (pinfunction "12_12") (pintype "passive"))
    )
    (net (code "168") (name "unconnected-(JP1-Pad13)") (class "Default")
      (node (ref "JP1") (pin "13") (pinfunction "13_13") (pintype "passive"))
    )
    (net (code "169") (name "unconnected-(JP1-Pad14)") (class "Default")
      (node (ref "JP1") (pin "14") (pinfunction "14_14") (pintype "passive"))
    )
    (net (code "170") (name "unconnected-(JP1-Pad15)") (class "Default")
      (node (ref "JP1") (pin "15") (pinfunction "15_15") (pintype "passive"))
    )
    (net (code "171") (name "unconnected-(JP1-Pad16)") (class "Default")
      (node (ref "JP1") (pin "16") (pinfunction "16_16") (pintype "passive"))
    )
    (net (code "172") (name "unconnected-(JP1-Pad17)") (class "Default")
      (node (ref "JP1") (pin "17") (pinfunction "17_17") (pintype "passive"))
    )
    (net (code "173") (name "unconnected-(JP1-Pad18)") (class "Default")
      (node (ref "JP1") (pin "18") (pinfunction "18_18") (pintype "passive"))
    )
    (net (code "174") (name "unconnected-(JP1-Pad19)") (class "Default")
      (node (ref "JP1") (pin "19") (pinfunction "19_19") (pintype "passive"))
    )
    (net (code "175") (name "unconnected-(JP1-Pad20)") (class "Default")
      (node (ref "JP1") (pin "20") (pinfunction "20_20") (pintype "passive"))
    )
    (net (code "176") (name "unconnected-(REG1.2-VOUT2-Pad2)") (class "Default")
      (node (ref "REG1.2") (pin "2") (pinfunction "VOUT2_2") (pintype "bidirectional"))
    )
    (net (code "177") (name "unconnected-(REG2.5-VOUT2-Pad2)") (class "Default")
      (node (ref "REG2.5") (pin "2") (pinfunction "VOUT2_2") (pintype "bidirectional"))
    )
    (net (code "178") (name "unconnected-(SV2-Pad1)") (class "Default")
      (node (ref "SV2") (pin "1") (pinfunction "1_1") (pintype "passive"))
    )
    (net (code "179") (name "unconnected-(SV2-Pad2)") (class "Default")
      (node (ref "SV2") (pin "2") (pinfunction "2_2") (pintype "passive"))
    )
    (net (code "180") (name "unconnected-(SV2-Pad3)") (class "Default")
      (node (ref "SV2") (pin "3") (pinfunction "3_3") (pintype "passive"))
    )
    (net (code "181") (name "unconnected-(SV2-Pad4)") (class "Default")
      (node (ref "SV2") (pin "4") (pinfunction "4_4") (pintype "passive"))
    )
    (net (code "182") (name "unconnected-(SV2-Pad5)") (class "Default")
      (node (ref "SV2") (pin "5") (pinfunction "5_5") (pintype "passive"))
    )
    (net (code "183") (name "unconnected-(SV2-Pad6)") (class "Default")
      (node (ref "SV2") (pin "6") (pinfunction "6_6") (pintype "passive"))
    )
    (net (code "184") (name "unconnected-(SV2-Pad7)") (class "Default")
      (node (ref "SV2") (pin "7") (pinfunction "7_7") (pintype "passive"))
    )
    (net (code "185") (name "unconnected-(SV2-Pad8)") (class "Default")
      (node (ref "SV2") (pin "8") (pinfunction "8_8") (pintype "passive"))
    )
    (net (code "186") (name "unconnected-(SV2-Pad9)") (class "Default")
      (node (ref "SV2") (pin "9") (pinfunction "9_9") (pintype "passive"))
    )
    (net (code "187") (name "unconnected-(SV2-Pad10)") (class "Default")
      (node (ref "SV2") (pin "10") (pinfunction "10_10") (pintype "passive"))
    )
    (net (code "188") (name "unconnected-(SV2-Pad11)") (class "Default")
      (node (ref "SV2") (pin "11") (pinfunction "11_11") (pintype "passive"))
    )
    (net (code "189") (name "unconnected-(SV2-Pad12)") (class "Default")
      (node (ref "SV2") (pin "12") (pinfunction "12_12") (pintype "passive"))
    )
    (net (code "190") (name "unconnected-(U$2-TRI-PadENA)") (class "Default")
      (node (ref "U$2") (pin "ENA") (pinfunction "TRI_ENA") (pintype "input"))
    )
    (net (code "191") (name "unconnected-(U$4-VOUT2-Pad2)") (class "Default")
      (node (ref "U$4") (pin "2") (pinfunction "VOUT2_2") (pintype "bidirectional"))
    )
    (net (code "192") (name "unconnected-(U1A-IO_L27P_0-PadP135)") (class "Default")
      (node (ref "U1") (pin "P135") (pinfunction "IO_L27P_0_P135") (pintype "bidirectional"))
    )
    (net (code "193") (name "unconnected-(U1A-IO_L30N_0-PadP132)") (class "Default")
      (node (ref "U1") (pin "P132") (pinfunction "IO_L30N_0_P132") (pintype "bidirectional"))
    )
    (net (code "194") (name "unconnected-(U1A-IO_L30P_0-PadP131)") (class "Default")
      (node (ref "U1") (pin "P131") (pinfunction "IO_L30P_0_P131") (pintype "bidirectional"))
    )
    (net (code "195") (name "unconnected-(U1A-IO_L31N_0-PadP130)") (class "Default")
      (node (ref "U1") (pin "P130") (pinfunction "IO_L31N_0_P130") (pintype "bidirectional"))
    )
    (net (code "196") (name "unconnected-(U1A-IO_L31P_0VREF_0-PadP129)") (class "Default")
      (node (ref "U1") (pin "P129") (pinfunction "IO_L31P_0VREF_0_P129") (pintype "bidirectional"))
    )
    (net (code "197") (name "unconnected-(U1A-IO_L32N_0GCLK7-PadP128)") (class "Default")
      (node (ref "U1") (pin "P128") (pinfunction "IO_L32N_0GCLK7_P128") (pintype "bidirectional"))
    )
    (net (code "198") (name "unconnected-(U1A-IO_L32P_0GCLK6-PadP127)") (class "Default")
      (node (ref "U1") (pin "P127") (pinfunction "IO_L32P_0GCLK6_P127") (pintype "bidirectional"))
    )
    (net (code "199") (name "unconnected-(U1C-IO-PadP116)") (class "Default")
      (node (ref "U1") (pin "P116") (pinfunction "IO_P116") (pintype "bidirectional"))
    )
    (net (code "200") (name "unconnected-(U1C-IO_L01N_1VRP_1-PadP113)") (class "Default")
      (node (ref "U1") (pin "P113") (pinfunction "IO_L01N_1VRP_1_P113") (pintype "bidirectional"))
    )
    (net (code "201") (name "unconnected-(U1C-IO_L01P_1VRN_1-PadP112)") (class "Default")
      (node (ref "U1") (pin "P112") (pinfunction "IO_L01P_1VRN_1_P112") (pintype "bidirectional"))
    )
    (net (code "202") (name "unconnected-(U1C-IO_L28N_1-PadP119)") (class "Default")
      (node (ref "U1") (pin "P119") (pinfunction "IO_L28N_1_P119") (pintype "bidirectional"))
    )
    (net (code "203") (name "unconnected-(U1C-IO_L28P_1-PadP118)") (class "Default")
      (node (ref "U1") (pin "P118") (pinfunction "IO_L28P_1_P118") (pintype "bidirectional"))
    )
    (net (code "204") (name "unconnected-(U1C-IO_L31N_1VREF_1-PadP123)") (class "Default")
      (node (ref "U1") (pin "P123") (pinfunction "IO_L31N_1VREF_1_P123") (pintype "bidirectional"))
    )
    (net (code "205") (name "unconnected-(U1C-IO_L31P_1-PadP122)") (class "Default")
      (node (ref "U1") (pin "P122") (pinfunction "IO_L31P_1_P122") (pintype "bidirectional"))
    )
    (net (code "206") (name "unconnected-(U1C-IO_L32N_1GCLK5-PadP125)") (class "Default")
      (node (ref "U1") (pin "P125") (pinfunction "IO_L32N_1GCLK5_P125") (pintype "bidirectional"))
    )
    (net (code "207") (name "unconnected-(U1C-IO_L32P_1GCLK4-PadP124)") (class "Default")
      (node (ref "U1") (pin "P124") (pinfunction "IO_L32P_1GCLK4_P124") (pintype "bidirectional"))
    )
    (net (code "208") (name "unconnected-(U1D-IO_L01N_2VRP_2-PadP108)") (class "Default")
      (node (ref "U1") (pin "P108") (pinfunction "IO_L01N_2VRP_2_P108") (pintype "bidirectional"))
    )
    (net (code "209") (name "unconnected-(U1D-IO_L01P_2VRN_2-PadP107)") (class "Default")
      (node (ref "U1") (pin "P107") (pinfunction "IO_L01P_2VRN_2_P107") (pintype "bidirectional"))
    )
    (net (code "210") (name "unconnected-(U1D-IO_L20N_2-PadP105)") (class "Default")
      (node (ref "U1") (pin "P105") (pinfunction "IO_L20N_2_P105") (pintype "bidirectional"))
    )
    (net (code "211") (name "unconnected-(U1D-IO_L20P_2-PadP104)") (class "Default")
      (node (ref "U1") (pin "P104") (pinfunction "IO_L20P_2_P104") (pintype "bidirectional"))
    )
    (net (code "212") (name "unconnected-(U1D-IO_L21N_2-PadP103)") (class "Default")
      (node (ref "U1") (pin "P103") (pinfunction "IO_L21N_2_P103") (pintype "bidirectional"))
    )
    (net (code "213") (name "unconnected-(U1D-IO_L21P_2-PadP102)") (class "Default")
      (node (ref "U1") (pin "P102") (pinfunction "IO_L21P_2_P102") (pintype "bidirectional"))
    )
    (net (code "214") (name "unconnected-(U1D-IO_L22N_2-PadP100)") (class "Default")
      (node (ref "U1") (pin "P100") (pinfunction "IO_L22N_2_P100") (pintype "bidirectional"))
    )
    (net (code "215") (name "unconnected-(U1D-IO_L22P_2-PadP99)") (class "Default")
      (node (ref "U1") (pin "P99") (pinfunction "IO_L22P_2_P99") (pintype "bidirectional"))
    )
    (net (code "216") (name "unconnected-(U1D-IO_L23N_2VREF_2-PadP98)") (class "Default")
      (node (ref "U1") (pin "P98") (pinfunction "IO_L23N_2VREF_2_P98") (pintype "bidirectional"))
    )
    (net (code "217") (name "unconnected-(U1D-IO_L23P_2-PadP97)") (class "Default")
      (node (ref "U1") (pin "P97") (pinfunction "IO_L23P_2_P97") (pintype "bidirectional"))
    )
    (net (code "218") (name "unconnected-(U1D-IO_L24N_2-PadP96)") (class "Default")
      (node (ref "U1") (pin "P96") (pinfunction "IO_L24N_2_P96") (pintype "bidirectional"))
    )
    (net (code "219") (name "unconnected-(U1D-IO_L24P_2-PadP95)") (class "Default")
      (node (ref "U1") (pin "P95") (pinfunction "IO_L24P_2_P95") (pintype "bidirectional"))
    )
    (net (code "220") (name "unconnected-(U1D-IO_L40N_2-PadP93)") (class "Default")
      (node (ref "U1") (pin "P93") (pinfunction "IO_L40N_2_P93") (pintype "bidirectional"))
    )
    (net (code "221") (name "unconnected-(U1D-IO_L40P_2VREF_2-PadP92)") (class "Default")
      (node (ref "U1") (pin "P92") (pinfunction "IO_L40P_2VREF_2_P92") (pintype "bidirectional"))
    )
    (net (code "222") (name "unconnected-(U1F-IO-PadP76)") (class "Default")
      (node (ref "U1") (pin "P76") (pinfunction "IO_P76") (pintype "bidirectional"))
    )
    (net (code "223") (name "unconnected-(U1F-IO_L01N_3VRP_3-PadP74)") (class "Default")
      (node (ref "U1") (pin "P74") (pinfunction "IO_L01N_3VRP_3_P74") (pintype "bidirectional"))
    )
    (net (code "224") (name "unconnected-(U1F-IO_L01P_3VRN_3-PadP73)") (class "Default")
      (node (ref "U1") (pin "P73") (pinfunction "IO_L01P_3VRN_3_P73") (pintype "bidirectional"))
    )
    (net (code "225") (name "unconnected-(U1F-IO_L20N_3-PadP78)") (class "Default")
      (node (ref "U1") (pin "P78") (pinfunction "IO_L20N_3_P78") (pintype "bidirectional"))
    )
    (net (code "226") (name "unconnected-(U1F-IO_L20P_3-PadP77)") (class "Default")
      (node (ref "U1") (pin "P77") (pinfunction "IO_L20P_3_P77") (pintype "bidirectional"))
    )
    (net (code "227") (name "unconnected-(U1F-IO_L21N_3-PadP80)") (class "Default")
      (node (ref "U1") (pin "P80") (pinfunction "IO_L21N_3_P80") (pintype "bidirectional"))
    )
    (net (code "228") (name "unconnected-(U1F-IO_L21P_3-PadP79)") (class "Default")
      (node (ref "U1") (pin "P79") (pinfunction "IO_L21P_3_P79") (pintype "bidirectional"))
    )
    (net (code "229") (name "unconnected-(U1F-IO_L22N_3-PadP83)") (class "Default")
      (node (ref "U1") (pin "P83") (pinfunction "IO_L22N_3_P83") (pintype "bidirectional"))
    )
    (net (code "230") (name "unconnected-(U1F-IO_L22P_3-PadP82)") (class "Default")
      (node (ref "U1") (pin "P82") (pinfunction "IO_L22P_3_P82") (pintype "bidirectional"))
    )
    (net (code "231") (name "unconnected-(U1F-IO_L23N_3-PadP85)") (class "Default")
      (node (ref "U1") (pin "P85") (pinfunction "IO_L23N_3_P85") (pintype "bidirectional"))
    )
    (net (code "232") (name "unconnected-(U1F-IO_L23P_3VREF_3-PadP84)") (class "Default")
      (node (ref "U1") (pin "P84") (pinfunction "IO_L23P_3VREF_3_P84") (pintype "bidirectional"))
    )
    (net (code "233") (name "unconnected-(U1F-IO_L24N_3-PadP87)") (class "Default")
      (node (ref "U1") (pin "P87") (pinfunction "IO_L24N_3_P87") (pintype "bidirectional"))
    )
    (net (code "234") (name "unconnected-(U1F-IO_L24P_3-PadP86)") (class "Default")
      (node (ref "U1") (pin "P86") (pinfunction "IO_L24P_3_P86") (pintype "bidirectional"))
    )
    (net (code "235") (name "unconnected-(U1F-IO_L40N_3VREF_3-PadP90)") (class "Default")
      (node (ref "U1") (pin "P90") (pinfunction "IO_L40N_3VREF_3_P90") (pintype "bidirectional"))
    )
    (net (code "236") (name "unconnected-(U1F-IO_L40P_3-PadP89)") (class "Default")
      (node (ref "U1") (pin "P89") (pinfunction "IO_L40P_3_P89") (pintype "bidirectional"))
    )
    (net (code "237") (name "unconnected-(U1N-HSWAP_EN-PadP142)") (class "Default")
      (node (ref "U1") (pin "P142") (pinfunction "HSWAP_EN_P142") (pintype "bidirectional"))
    )
    (net (code "238") (name "unconnected-(X1-3-Pad2)") (class "Default")
      (node (ref "X1") (pin "2") (pinfunction "3_2") (pintype "passive"))
    )
    (net (code "239") (name "unconnected-(X2-Pad10)") (class "Default")
      (node (ref "X2") (pin "10") (pinfunction "10_10") (pintype "passive"))
    )
    (net (code "240") (name "unconnected-(X2-Pad12)") (class "Default")
      (node (ref "X2") (pin "12") (pinfunction "12_12") (pintype "passive"))
    )
    (net (code "241") (name "unconnected-(X3-Pad2)") (class "Default")
      (node (ref "X3") (pin "2") (pinfunction "2_2") (pintype "passive"))
    )
    (net (code "242") (name "unconnected-(X3-Pad8)") (class "Default")
      (node (ref "X3") (pin "8") (pinfunction "8_8") (pintype "passive"))
    )
    (net (code "243") (name "unconnected-(X4-PadG2)") (class "Default")
      (node (ref "X4") (pin "G2") (pinfunction "G2_G2") (pintype "passive"))
    )
    (net (code "244") (name "unconnected-(X5-PadG2)") (class "Default")
      (node (ref "X5") (pin "G2") (pinfunction "G2_G2") (pintype "passive"))
    )
    (net (code "245") (name "unconnected-(X6-Pad1)") (class "Default")
      (node (ref "X6") (pin "1") (pinfunction "1_1") (pintype "passive"))
    )
  )
)
